# PART1.net
KiCad netlist of a schematic drawn in Altium Designer
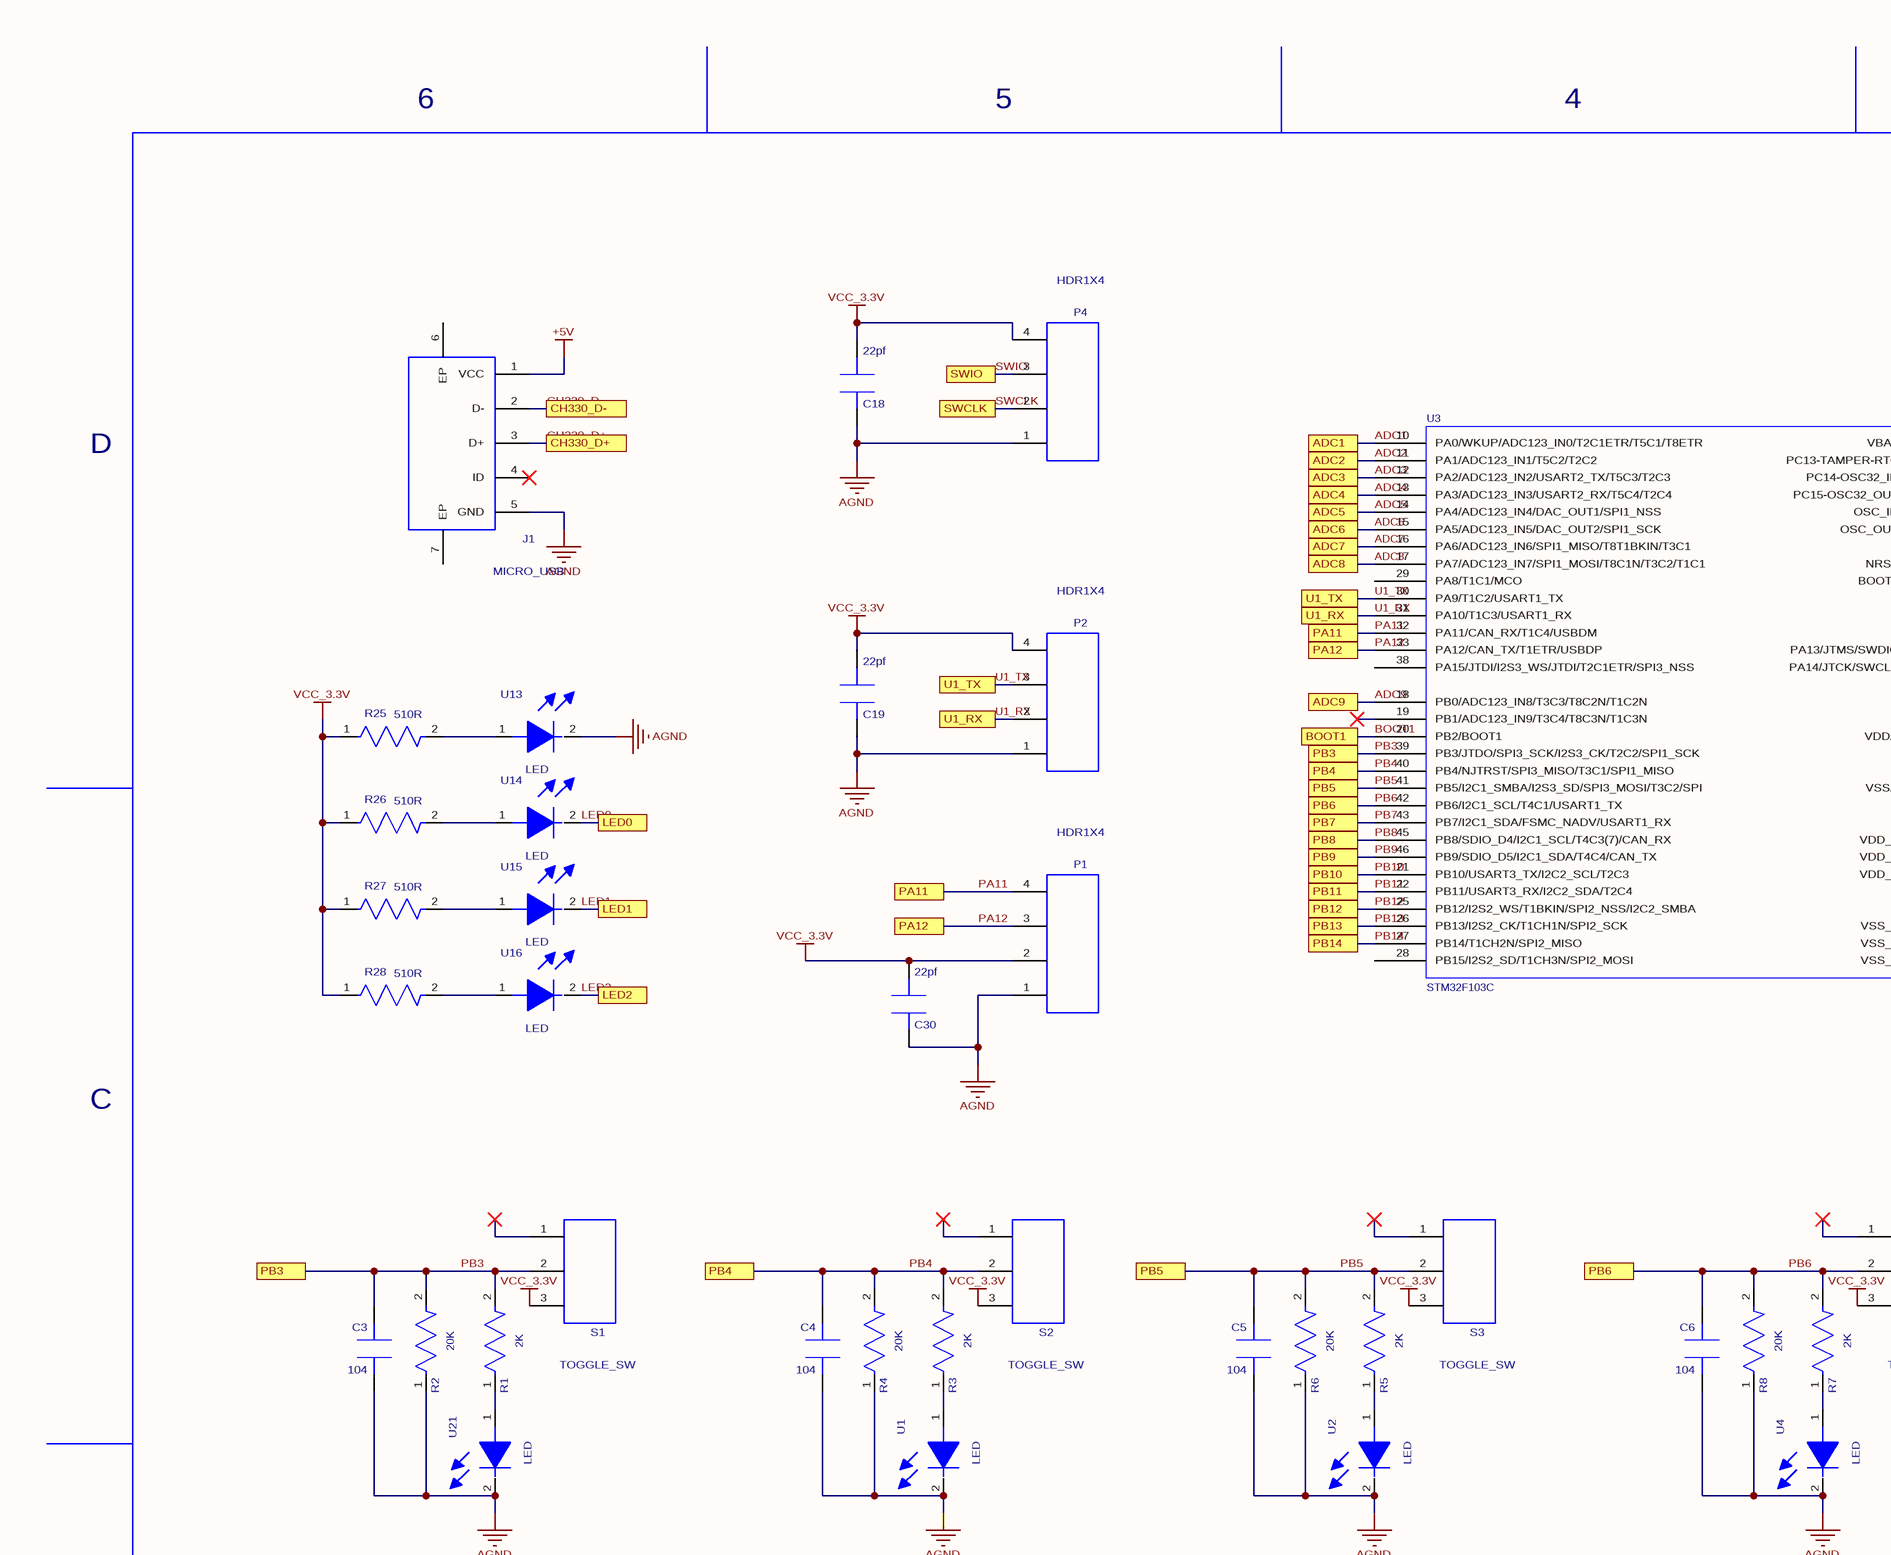
[diagram p0: PART1原.SchDoc, top left]
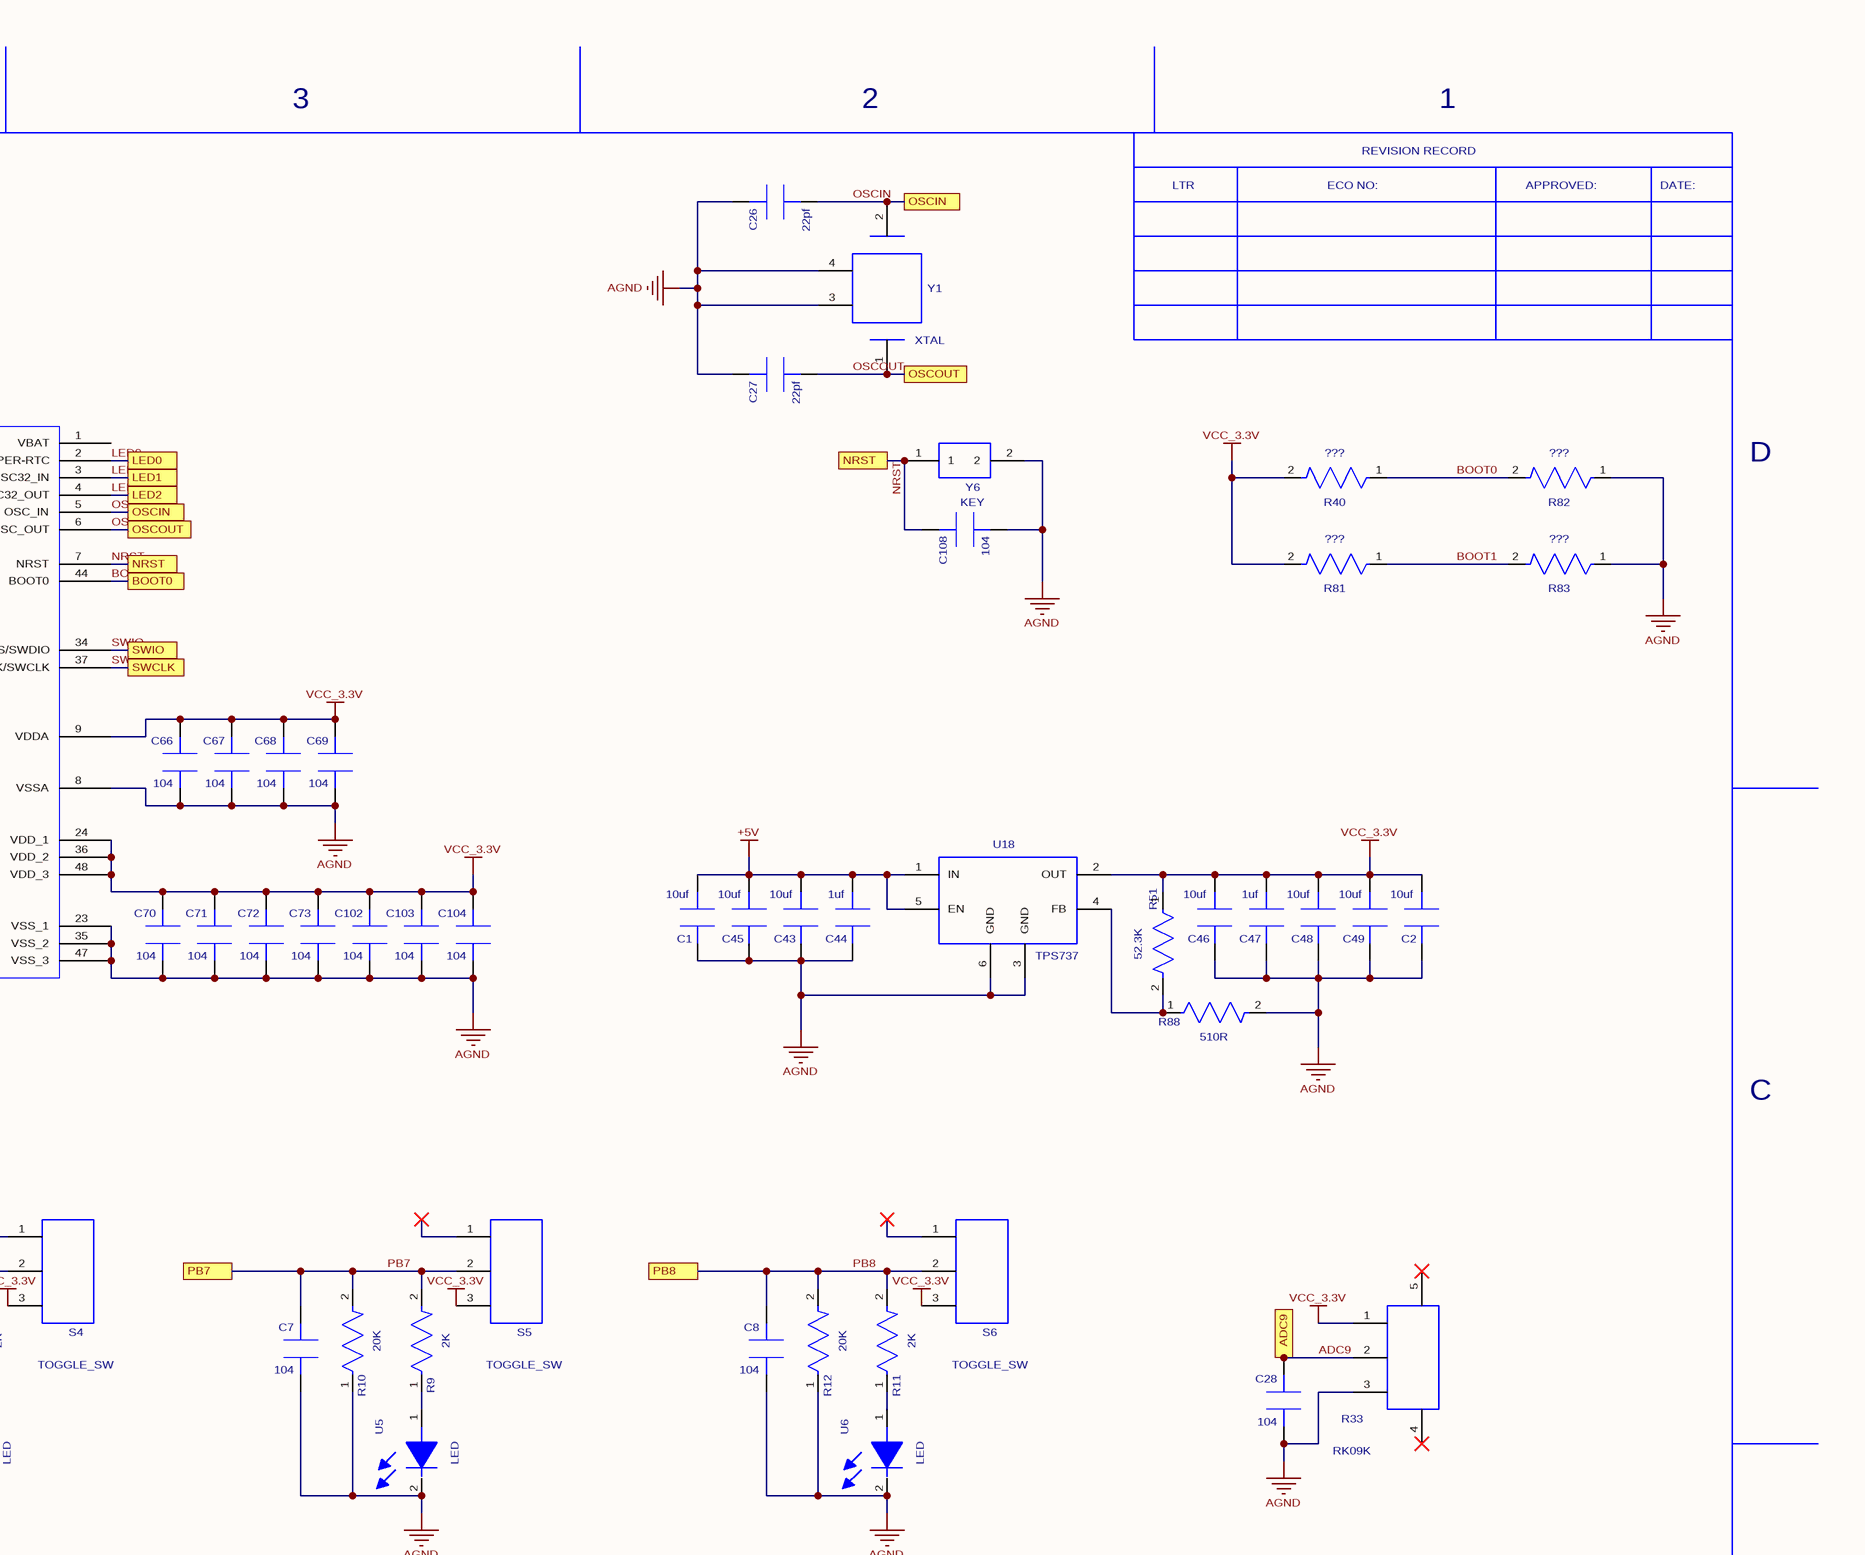
[diagram p1: PART1原.SchDoc, top right]
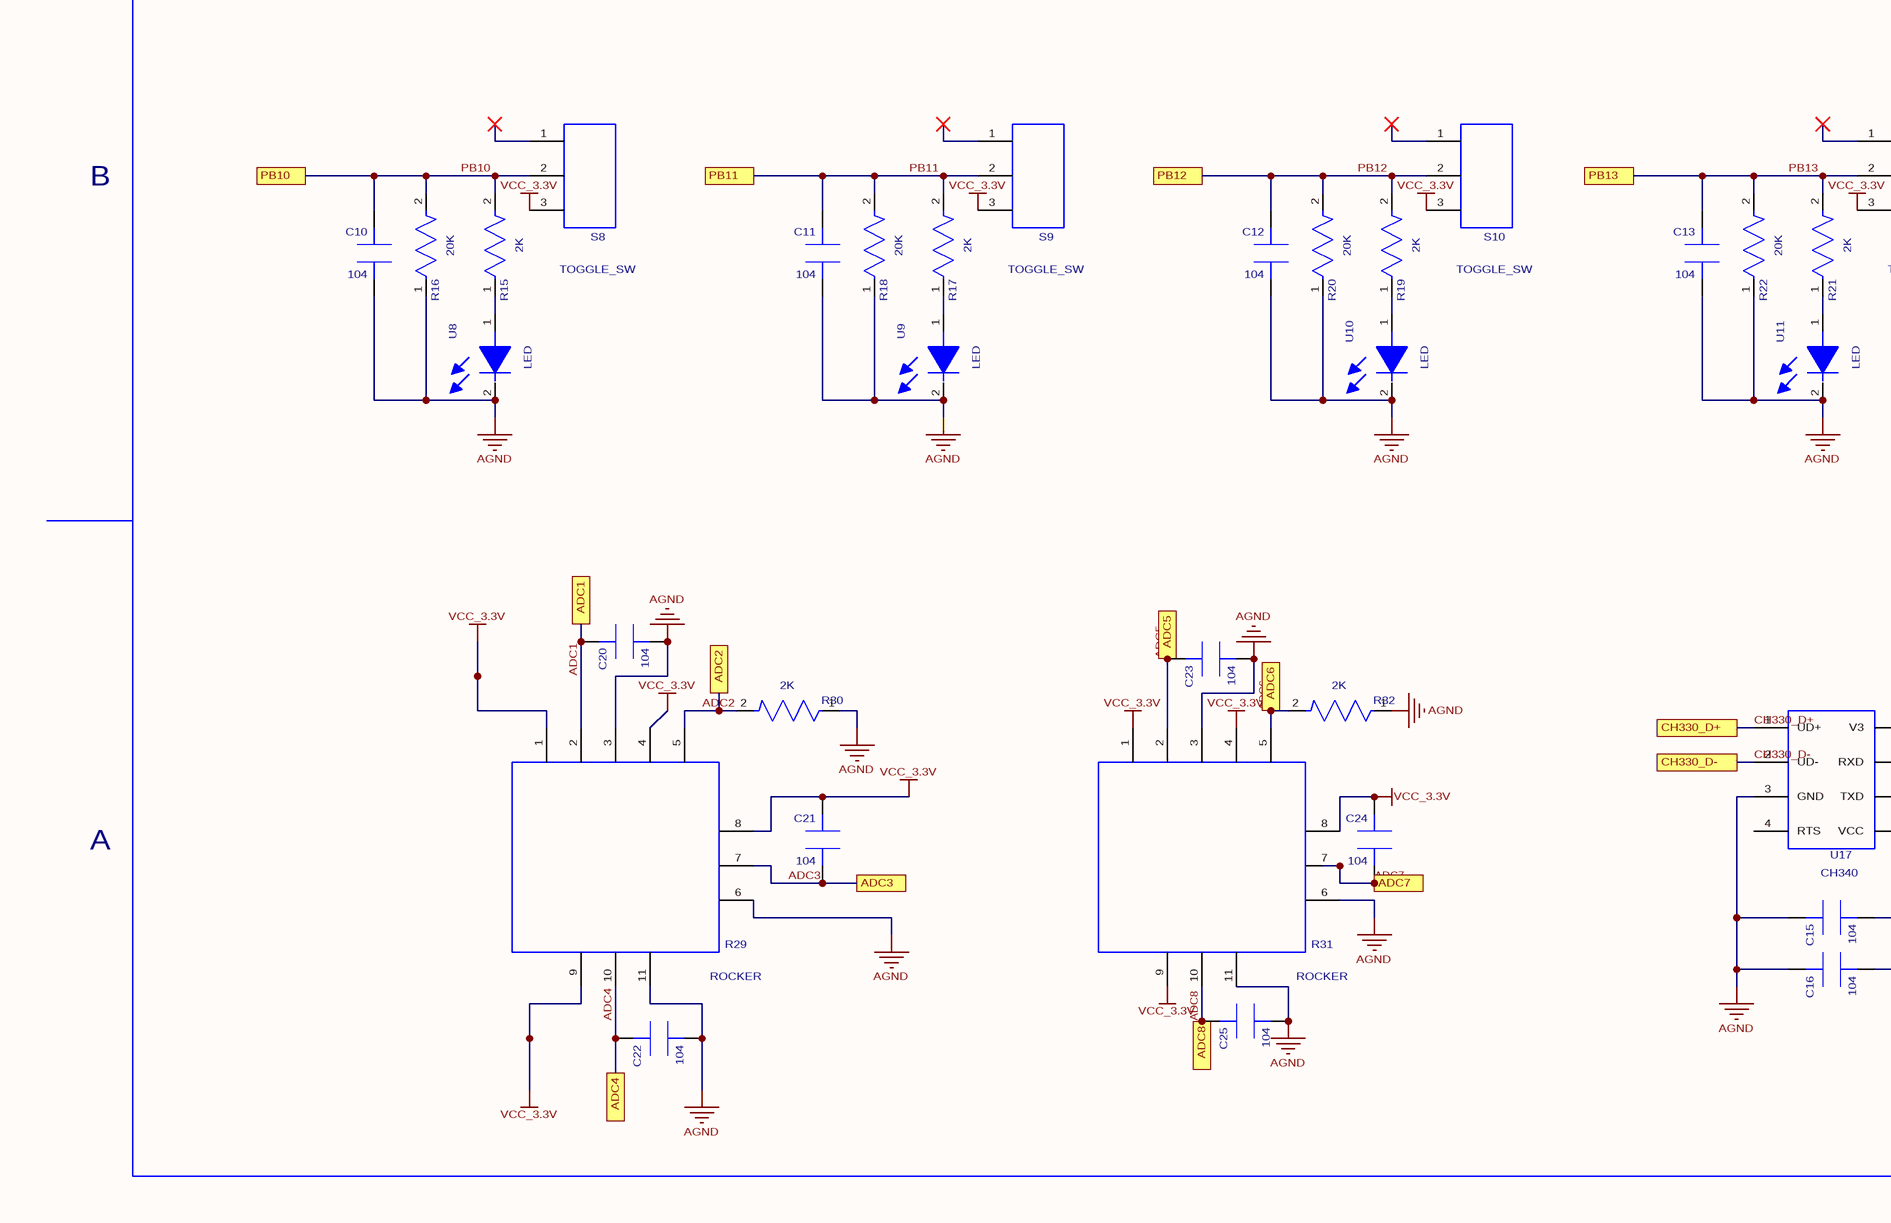
[diagram p2: PART1原.SchDoc, bottom left]
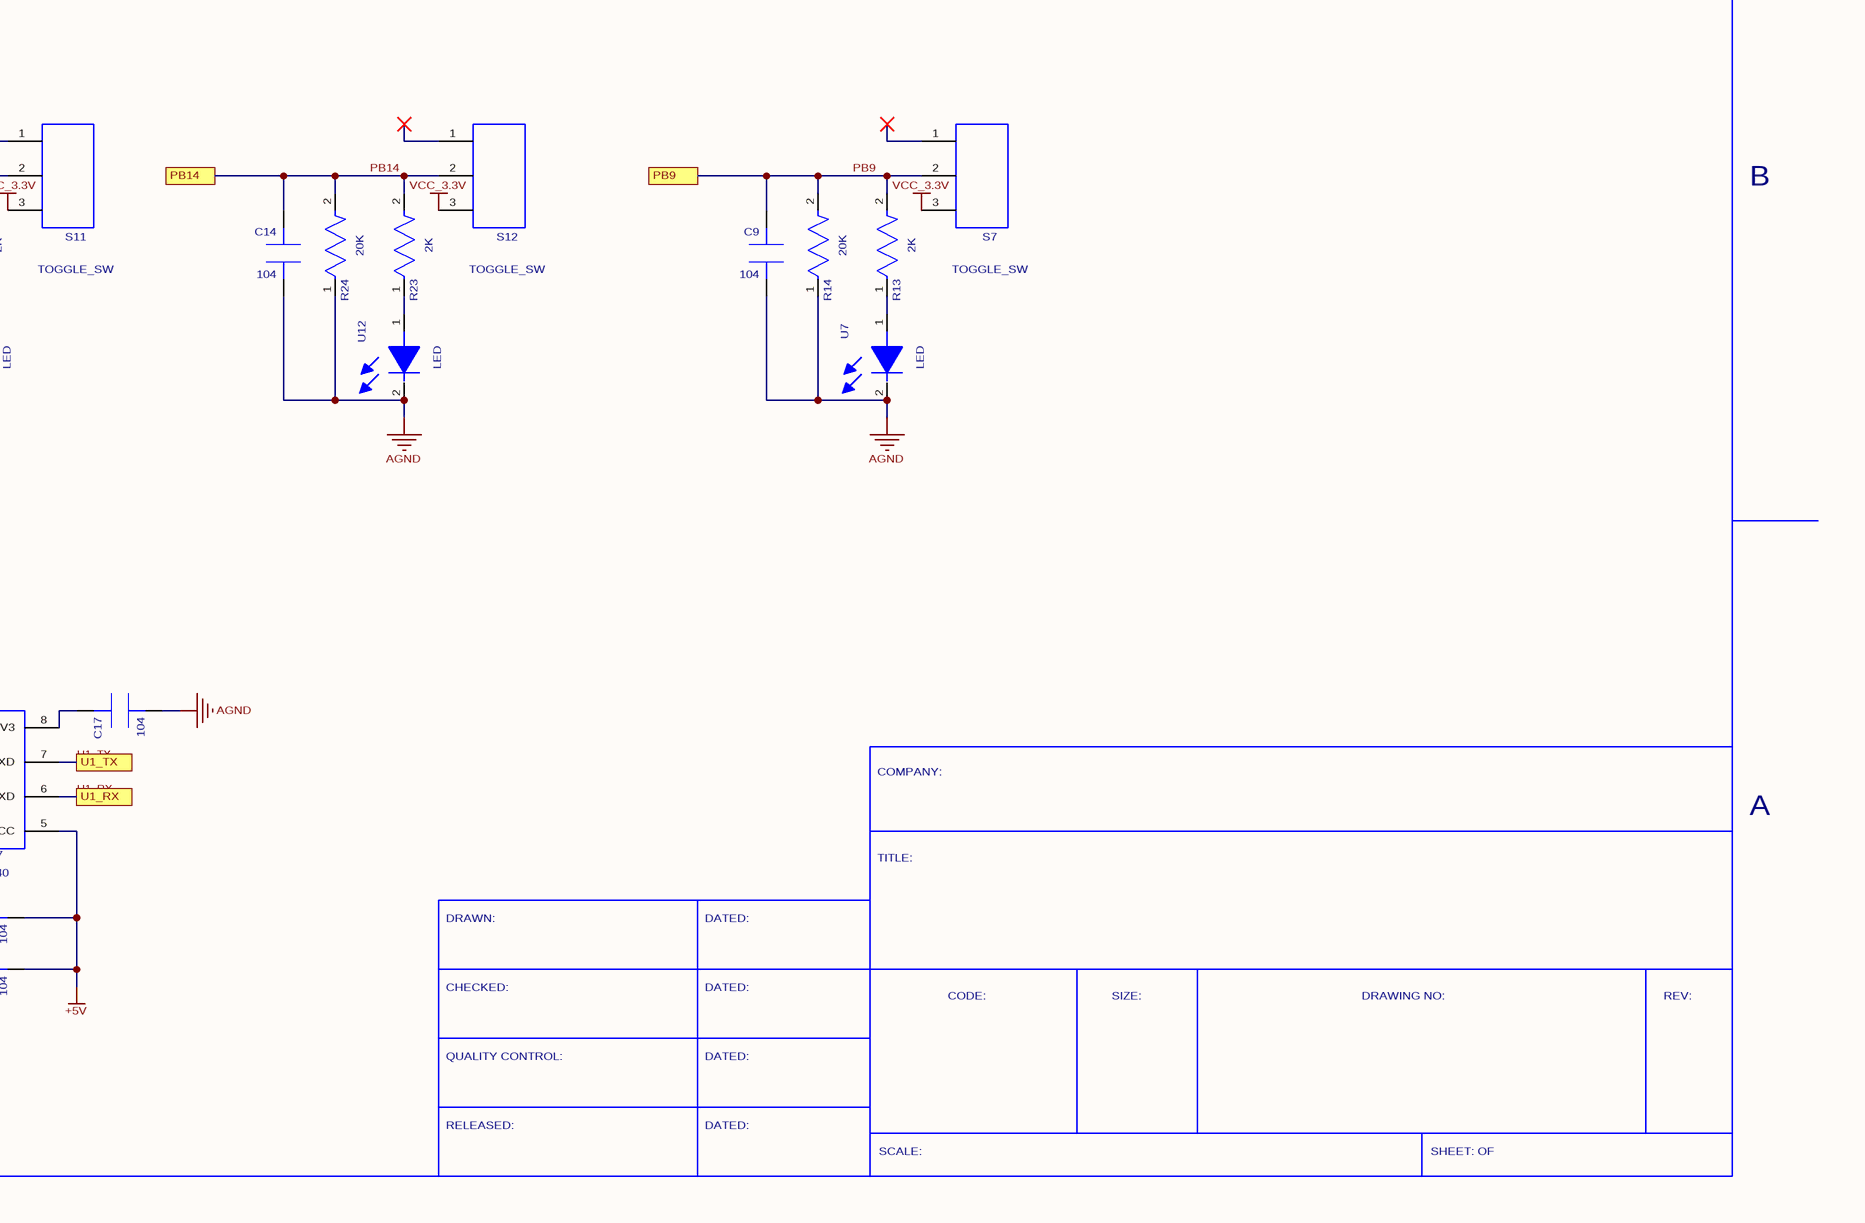
[diagram p3: PART1原.SchDoc, bottom right]

(export (version "E")
  (design (tool "Eeschema 10.0.6"))
  (components
    (comp (ref "C1")
      (value "10uf")
      (footprint "1206C")
      (description "RADIAL FILM CAPACITOR, MIL-SPEC SIZE CFR04R SIZE 'C'")
      (fields (field (name "TOLERANCE") "???") (field (name "PART NUMBER") "TBD"))
      (libsource (lib "*") (part "CAP-CFR04R-C"))
    )
    (comp (ref "C2")
      (value "10uf")
      (footprint "1206C")
      (description "RADIAL FILM CAPACITOR, MIL-SPEC SIZE CFR04R SIZE 'C'")
      (fields (field (name "TOLERANCE") "???") (field (name "PART NUMBER") "TBD"))
      (libsource (lib "*") (part "CAP-CFR04R-C"))
    )
    (comp (ref "C3")
      (value "104")
      (footprint "0603C")
      (description "RADIAL FILM CAPACITOR, MIL-SPEC SIZE CFR04R SIZE 'C'")
      (fields (field (name "TOLERANCE") "???") (field (name "PART NUMBER") "TBD"))
      (libsource (lib "*") (part "CAP-CFR04R-C"))
    )
    (comp (ref "C4")
      (value "104")
      (footprint "0603C")
      (description "RADIAL FILM CAPACITOR, MIL-SPEC SIZE CFR04R SIZE 'C'")
      (fields (field (name "TOLERANCE") "???") (field (name "PART NUMBER") "TBD"))
      (libsource (lib "*") (part "CAP-CFR04R-C"))
    )
    (comp (ref "C5")
      (value "104")
      (footprint "0603C")
      (description "RADIAL FILM CAPACITOR, MIL-SPEC SIZE CFR04R SIZE 'C'")
      (fields (field (name "TOLERANCE") "???") (field (name "PART NUMBER") "TBD"))
      (libsource (lib "*") (part "CAP-CFR04R-C"))
    )
    (comp (ref "C6")
      (value "104")
      (footprint "0603C")
      (description "RADIAL FILM CAPACITOR, MIL-SPEC SIZE CFR04R SIZE 'C'")
      (fields (field (name "TOLERANCE") "???") (field (name "PART NUMBER") "TBD"))
      (libsource (lib "*") (part "CAP-CFR04R-C"))
    )
    (comp (ref "C7")
      (value "104")
      (footprint "0603C")
      (description "RADIAL FILM CAPACITOR, MIL-SPEC SIZE CFR04R SIZE 'C'")
      (fields (field (name "TOLERANCE") "???") (field (name "PART NUMBER") "TBD"))
      (libsource (lib "*") (part "CAP-CFR04R-C"))
    )
    (comp (ref "C8")
      (value "104")
      (footprint "0603C")
      (description "RADIAL FILM CAPACITOR, MIL-SPEC SIZE CFR04R SIZE 'C'")
      (fields (field (name "TOLERANCE") "???") (field (name "PART NUMBER") "TBD"))
      (libsource (lib "*") (part "CAP-CFR04R-C"))
    )
    (comp (ref "C9")
      (value "104")
      (footprint "0603C")
      (description "RADIAL FILM CAPACITOR, MIL-SPEC SIZE CFR04R SIZE 'C'")
      (fields (field (name "TOLERANCE") "???") (field (name "PART NUMBER") "TBD"))
      (libsource (lib "*") (part "CAP-CFR04R-C"))
    )
    (comp (ref "C10")
      (value "104")
      (footprint "0603C")
      (description "RADIAL FILM CAPACITOR, MIL-SPEC SIZE CFR04R SIZE 'C'")
      (fields (field (name "TOLERANCE") "???") (field (name "PART NUMBER") "TBD"))
      (libsource (lib "*") (part "CAP-CFR04R-C"))
    )
    (comp (ref "C11")
      (value "104")
      (footprint "0603C")
      (description "RADIAL FILM CAPACITOR, MIL-SPEC SIZE CFR04R SIZE 'C'")
      (fields (field (name "TOLERANCE") "???") (field (name "PART NUMBER") "TBD"))
      (libsource (lib "*") (part "CAP-CFR04R-C"))
    )
    (comp (ref "C12")
      (value "104")
      (footprint "0603C")
      (description "RADIAL FILM CAPACITOR, MIL-SPEC SIZE CFR04R SIZE 'C'")
      (fields (field (name "TOLERANCE") "???") (field (name "PART NUMBER") "TBD"))
      (libsource (lib "*") (part "CAP-CFR04R-C"))
    )
    (comp (ref "C13")
      (value "104")
      (footprint "0603C")
      (description "RADIAL FILM CAPACITOR, MIL-SPEC SIZE CFR04R SIZE 'C'")
      (fields (field (name "TOLERANCE") "???") (field (name "PART NUMBER") "TBD"))
      (libsource (lib "*") (part "CAP-CFR04R-C"))
    )
    (comp (ref "C14")
      (value "104")
      (footprint "0603C")
      (description "RADIAL FILM CAPACITOR, MIL-SPEC SIZE CFR04R SIZE 'C'")
      (fields (field (name "TOLERANCE") "???") (field (name "PART NUMBER") "TBD"))
      (libsource (lib "*") (part "CAP-CFR04R-C"))
    )
    (comp (ref "C15")
      (value "104")
      (footprint "0603C")
      (description "RADIAL FILM CAPACITOR, MIL-SPEC SIZE CFR04R SIZE 'C'")
      (fields (field (name "TOLERANCE") "???") (field (name "PART NUMBER") "TBD"))
      (libsource (lib "*") (part "CAP-CFR04R-C"))
    )
    (comp (ref "C16")
      (value "104")
      (footprint "0805C")
      (description "RADIAL FILM CAPACITOR, MIL-SPEC SIZE CFR04R SIZE 'C'")
      (fields (field (name "TOLERANCE") "???") (field (name "PART NUMBER") "TBD"))
      (libsource (lib "*") (part "CAP-CFR04R-C"))
    )
    (comp (ref "C17")
      (value "104")
      (footprint "0603C")
      (description "RADIAL FILM CAPACITOR, MIL-SPEC SIZE CFR04R SIZE 'C'")
      (fields (field (name "TOLERANCE") "???") (field (name "PART NUMBER") "TBD"))
      (libsource (lib "*") (part "CAP-CFR04R-C"))
    )
    (comp (ref "C18")
      (value "22pf")
      (footprint "0603C")
      (description "RADIAL FILM CAPACITOR, MIL-SPEC SIZE CFR04R SIZE 'C'")
      (fields (field (name "TOLERANCE") "???") (field (name "PART NUMBER") "TBD"))
      (libsource (lib "*") (part "CAP-CFR04R-C"))
    )
    (comp (ref "C19")
      (value "22pf")
      (footprint "0603C")
      (description "RADIAL FILM CAPACITOR, MIL-SPEC SIZE CFR04R SIZE 'C'")
      (fields (field (name "TOLERANCE") "???") (field (name "PART NUMBER") "TBD"))
      (libsource (lib "*") (part "CAP-CFR04R-C"))
    )
    (comp (ref "C20")
      (value "104")
      (footprint "0805C")
      (description "RADIAL FILM CAPACITOR, MIL-SPEC SIZE CFR04R SIZE 'C'")
      (fields (field (name "TOLERANCE") "???") (field (name "PART NUMBER") "TBD"))
      (libsource (lib "*") (part "CAP-CFR04R-C"))
    )
    (comp (ref "C21")
      (value "104")
      (footprint "0805C")
      (description "RADIAL FILM CAPACITOR, MIL-SPEC SIZE CFR04R SIZE 'C'")
      (fields (field (name "TOLERANCE") "???") (field (name "PART NUMBER") "TBD"))
      (libsource (lib "*") (part "CAP-CFR04R-C"))
    )
    (comp (ref "C22")
      (value "104")
      (footprint "0805C")
      (description "RADIAL FILM CAPACITOR, MIL-SPEC SIZE CFR04R SIZE 'C'")
      (fields (field (name "TOLERANCE") "???") (field (name "PART NUMBER") "TBD"))
      (libsource (lib "*") (part "CAP-CFR04R-C"))
    )
    (comp (ref "C23")
      (value "104")
      (footprint "0805C")
      (description "RADIAL FILM CAPACITOR, MIL-SPEC SIZE CFR04R SIZE 'C'")
      (fields (field (name "TOLERANCE") "???") (field (name "PART NUMBER") "TBD"))
      (libsource (lib "*") (part "CAP-CFR04R-C"))
    )
    (comp (ref "C24")
      (value "104")
      (footprint "0805C")
      (description "RADIAL FILM CAPACITOR, MIL-SPEC SIZE CFR04R SIZE 'C'")
      (fields (field (name "TOLERANCE") "???") (field (name "PART NUMBER") "TBD"))
      (libsource (lib "*") (part "CAP-CFR04R-C"))
    )
    (comp (ref "C25")
      (value "104")
      (footprint "0805C")
      (description "RADIAL FILM CAPACITOR, MIL-SPEC SIZE CFR04R SIZE 'C'")
      (fields (field (name "TOLERANCE") "???") (field (name "PART NUMBER") "TBD"))
      (libsource (lib "*") (part "CAP-CFR04R-C"))
    )
    (comp (ref "C26")
      (value "22pf")
      (footprint "0603C")
      (description "RADIAL FILM CAPACITOR, MIL-SPEC SIZE CFR04R SIZE 'C'")
      (fields (field (name "TOLERANCE") "???") (field (name "PART NUMBER") "TBD"))
      (libsource (lib "*") (part "CAP-CFR04R-C"))
    )
    (comp (ref "C27")
      (value "22pf")
      (footprint "0603C")
      (description "RADIAL FILM CAPACITOR, MIL-SPEC SIZE CFR04R SIZE 'C'")
      (fields (field (name "TOLERANCE") "???") (field (name "PART NUMBER") "TBD"))
      (libsource (lib "*") (part "CAP-CFR04R-C"))
    )
    (comp (ref "C28")
      (value "104")
      (footprint "0603C")
      (description "RADIAL FILM CAPACITOR, MIL-SPEC SIZE CFR04R SIZE 'C'")
      (fields (field (name "TOLERANCE") "???") (field (name "PART NUMBER") "TBD"))
      (libsource (lib "*") (part "CAP-CFR04R-C"))
    )
    (comp (ref "C30")
      (value "22pf")
      (footprint "0603C")
      (description "RADIAL FILM CAPACITOR, MIL-SPEC SIZE CFR04R SIZE 'C'")
      (fields (field (name "TOLERANCE") "???") (field (name "PART NUMBER") "TBD"))
      (libsource (lib "*") (part "CAP-CFR04R-C"))
    )
    (comp (ref "C43")
      (value "10uf")
      (footprint "1206C")
      (description "RADIAL FILM CAPACITOR, MIL-SPEC SIZE CFR04R SIZE 'C'")
      (fields (field (name "TOLERANCE") "???") (field (name "PART NUMBER") "TBD"))
      (libsource (lib "*") (part "CAP-CFR04R-C"))
    )
    (comp (ref "C44")
      (value "1uf")
      (footprint "0805C")
      (description "RADIAL FILM CAPACITOR, MIL-SPEC SIZE CFR04R SIZE 'C'")
      (fields (field (name "TOLERANCE") "???") (field (name "PART NUMBER") "TBD"))
      (libsource (lib "*") (part "CAP-CFR04R-C"))
    )
    (comp (ref "C45")
      (value "10uf")
      (footprint "1206C")
      (description "RADIAL FILM CAPACITOR, MIL-SPEC SIZE CFR04R SIZE 'C'")
      (fields (field (name "TOLERANCE") "???") (field (name "PART NUMBER") "TBD"))
      (libsource (lib "*") (part "CAP-CFR04R-C"))
    )
    (comp (ref "C46")
      (value "10uf")
      (footprint "1206C")
      (description "RADIAL FILM CAPACITOR, MIL-SPEC SIZE CFR04R SIZE 'C'")
      (fields (field (name "TOLERANCE") "???") (field (name "PART NUMBER") "TBD"))
      (libsource (lib "*") (part "CAP-CFR04R-C"))
    )
    (comp (ref "C47")
      (value "1uf")
      (footprint "0805C")
      (description "RADIAL FILM CAPACITOR, MIL-SPEC SIZE CFR04R SIZE 'C'")
      (fields (field (name "TOLERANCE") "???") (field (name "PART NUMBER") "TBD"))
      (libsource (lib "*") (part "CAP-CFR04R-C"))
    )
    (comp (ref "C48")
      (value "10uf")
      (footprint "1206C")
      (description "RADIAL FILM CAPACITOR, MIL-SPEC SIZE CFR04R SIZE 'C'")
      (fields (field (name "TOLERANCE") "???") (field (name "PART NUMBER") "TBD"))
      (libsource (lib "*") (part "CAP-CFR04R-C"))
    )
    (comp (ref "C49")
      (value "10uf")
      (footprint "1206C")
      (description "RADIAL FILM CAPACITOR, MIL-SPEC SIZE CFR04R SIZE 'C'")
      (fields (field (name "TOLERANCE") "???") (field (name "PART NUMBER") "TBD"))
      (libsource (lib "*") (part "CAP-CFR04R-C"))
    )
    (comp (ref "C66")
      (value "104")
      (footprint "0805C")
      (description "RADIAL FILM CAPACITOR, MIL-SPEC SIZE CFR04R SIZE 'C'")
      (fields (field (name "TOLERANCE") "???") (field (name "PART NUMBER") "TBD"))
      (libsource (lib "*") (part "CAP-CFR04R-C"))
    )
    (comp (ref "C67")
      (value "104")
      (footprint "0805C")
      (description "RADIAL FILM CAPACITOR, MIL-SPEC SIZE CFR04R SIZE 'C'")
      (fields (field (name "TOLERANCE") "???") (field (name "PART NUMBER") "TBD"))
      (libsource (lib "*") (part "CAP-CFR04R-C"))
    )
    (comp (ref "C68")
      (value "104")
      (footprint "0805C")
      (description "RADIAL FILM CAPACITOR, MIL-SPEC SIZE CFR04R SIZE 'C'")
      (fields (field (name "TOLERANCE") "???") (field (name "PART NUMBER") "TBD"))
      (libsource (lib "*") (part "CAP-CFR04R-C"))
    )
    (comp (ref "C69")
      (value "104")
      (footprint "0805C")
      (description "RADIAL FILM CAPACITOR, MIL-SPEC SIZE CFR04R SIZE 'C'")
      (fields (field (name "TOLERANCE") "???") (field (name "PART NUMBER") "TBD"))
      (libsource (lib "*") (part "CAP-CFR04R-C"))
    )
    (comp (ref "C70")
      (value "104")
      (footprint "0805C")
      (description "RADIAL FILM CAPACITOR, MIL-SPEC SIZE CFR04R SIZE 'C'")
      (fields (field (name "TOLERANCE") "???") (field (name "PART NUMBER") "TBD"))
      (libsource (lib "*") (part "CAP-CFR04R-C"))
    )
    (comp (ref "C71")
      (value "104")
      (footprint "0805C")
      (description "RADIAL FILM CAPACITOR, MIL-SPEC SIZE CFR04R SIZE 'C'")
      (fields (field (name "TOLERANCE") "???") (field (name "PART NUMBER") "TBD"))
      (libsource (lib "*") (part "CAP-CFR04R-C"))
    )
    (comp (ref "C72")
      (value "104")
      (footprint "0805C")
      (description "RADIAL FILM CAPACITOR, MIL-SPEC SIZE CFR04R SIZE 'C'")
      (fields (field (name "TOLERANCE") "???") (field (name "PART NUMBER") "TBD"))
      (libsource (lib "*") (part "CAP-CFR04R-C"))
    )
    (comp (ref "C73")
      (value "104")
      (footprint "0805C")
      (description "RADIAL FILM CAPACITOR, MIL-SPEC SIZE CFR04R SIZE 'C'")
      (fields (field (name "TOLERANCE") "???") (field (name "PART NUMBER") "TBD"))
      (libsource (lib "*") (part "CAP-CFR04R-C"))
    )
    (comp (ref "C102")
      (value "104")
      (footprint "0805C")
      (description "RADIAL FILM CAPACITOR, MIL-SPEC SIZE CFR04R SIZE 'C'")
      (fields (field (name "TOLERANCE") "???") (field (name "PART NUMBER") "TBD"))
      (libsource (lib "*") (part "CAP-CFR04R-C"))
    )
    (comp (ref "C103")
      (value "104")
      (footprint "0805C")
      (description "RADIAL FILM CAPACITOR, MIL-SPEC SIZE CFR04R SIZE 'C'")
      (fields (field (name "TOLERANCE") "???") (field (name "PART NUMBER") "TBD"))
      (libsource (lib "*") (part "CAP-CFR04R-C"))
    )
    (comp (ref "C104")
      (value "104")
      (footprint "0805C")
      (description "RADIAL FILM CAPACITOR, MIL-SPEC SIZE CFR04R SIZE 'C'")
      (fields (field (name "TOLERANCE") "???") (field (name "PART NUMBER") "TBD"))
      (libsource (lib "*") (part "CAP-CFR04R-C"))
    )
    (comp (ref "C108")
      (value "104")
      (footprint "0805C")
      (description "RADIAL FILM CAPACITOR, MIL-SPEC SIZE CFR04R SIZE 'C'")
      (fields (field (name "TOLERANCE") "???") (field (name "PART NUMBER") "TBD"))
      (libsource (lib "*") (part "CAP-CFR04R-C"))
    )
    (comp (ref "J1") (value "MICRO_USB") (footprint "MICRO_USB") (libsource (lib "*") (part "MICRO_USB")))
    (comp (ref "P1") (value "HDR1X4") (footprint "HDR1X4(2)") (libsource (lib "*") (part "HDR1X4")))
    (comp (ref "P2") (value "HDR1X4") (footprint "HDR1X4(2)") (libsource (lib "*") (part "HDR1X4")))
    (comp (ref "P4") (value "HDR1X4") (footprint "HDR1X4(2)") (libsource (lib "*") (part "HDR1X4")))
    (comp (ref "R1")
      (value "2K")
      (footprint "0603R")
      (description "WIRE WOUND RESISTOR 3.4 X 7.05 MM")
      (fields (field (name "Comment") "RES-WR1"))
      (libsource (lib "*") (part "RES-WR1"))
    )
    (comp (ref "R2")
      (value "20K")
      (footprint "0603R")
      (description "WIRE WOUND RESISTOR 3.4 X 7.05 MM")
      (fields (field (name "Comment") "RES-WR1"))
      (libsource (lib "*") (part "RES-WR1"))
    )
    (comp (ref "R3")
      (value "2K")
      (footprint "0603R")
      (description "WIRE WOUND RESISTOR 3.4 X 7.05 MM")
      (fields (field (name "Comment") "RES-WR1"))
      (libsource (lib "*") (part "RES-WR1"))
    )
    (comp (ref "R4")
      (value "20K")
      (footprint "0603R")
      (description "WIRE WOUND RESISTOR 3.4 X 7.05 MM")
      (fields (field (name "Comment") "RES-WR1"))
      (libsource (lib "*") (part "RES-WR1"))
    )
    (comp (ref "R5")
      (value "2K")
      (footprint "0603R")
      (description "WIRE WOUND RESISTOR 3.4 X 7.05 MM")
      (fields (field (name "Comment") "RES-WR1"))
      (libsource (lib "*") (part "RES-WR1"))
    )
    (comp (ref "R6")
      (value "20K")
      (footprint "0603R")
      (description "WIRE WOUND RESISTOR 3.4 X 7.05 MM")
      (fields (field (name "Comment") "RES-WR1"))
      (libsource (lib "*") (part "RES-WR1"))
    )
    (comp (ref "R7")
      (value "2K")
      (footprint "0603R")
      (description "WIRE WOUND RESISTOR 3.4 X 7.05 MM")
      (fields (field (name "Comment") "RES-WR1"))
      (libsource (lib "*") (part "RES-WR1"))
    )
    (comp (ref "R8")
      (value "20K")
      (footprint "0603R")
      (description "WIRE WOUND RESISTOR 3.4 X 7.05 MM")
      (fields (field (name "Comment") "RES-WR1"))
      (libsource (lib "*") (part "RES-WR1"))
    )
    (comp (ref "R9")
      (value "2K")
      (footprint "0603R")
      (description "WIRE WOUND RESISTOR 3.4 X 7.05 MM")
      (fields (field (name "Comment") "RES-WR1"))
      (libsource (lib "*") (part "RES-WR1"))
    )
    (comp (ref "R10")
      (value "20K")
      (footprint "0603R")
      (description "WIRE WOUND RESISTOR 3.4 X 7.05 MM")
      (fields (field (name "Comment") "RES-WR1"))
      (libsource (lib "*") (part "RES-WR1"))
    )
    (comp (ref "R11")
      (value "2K")
      (footprint "0603R")
      (description "WIRE WOUND RESISTOR 3.4 X 7.05 MM")
      (fields (field (name "Comment") "RES-WR1"))
      (libsource (lib "*") (part "RES-WR1"))
    )
    (comp (ref "R12")
      (value "20K")
      (footprint "0603R")
      (description "WIRE WOUND RESISTOR 3.4 X 7.05 MM")
      (fields (field (name "Comment") "RES-WR1"))
      (libsource (lib "*") (part "RES-WR1"))
    )
    (comp (ref "R13")
      (value "2K")
      (footprint "0603R")
      (description "WIRE WOUND RESISTOR 3.4 X 7.05 MM")
      (fields (field (name "Comment") "RES-WR1"))
      (libsource (lib "*") (part "RES-WR1"))
    )
    (comp (ref "R14")
      (value "20K")
      (footprint "0603R")
      (description "WIRE WOUND RESISTOR 3.4 X 7.05 MM")
      (fields (field (name "Comment") "RES-WR1"))
      (libsource (lib "*") (part "RES-WR1"))
    )
    (comp (ref "R15")
      (value "2K")
      (footprint "0603R")
      (description "WIRE WOUND RESISTOR 3.4 X 7.05 MM")
      (fields (field (name "Comment") "RES-WR1"))
      (libsource (lib "*") (part "RES-WR1"))
    )
    (comp (ref "R16")
      (value "20K")
      (footprint "0603R")
      (description "WIRE WOUND RESISTOR 3.4 X 7.05 MM")
      (fields (field (name "Comment") "RES-WR1"))
      (libsource (lib "*") (part "RES-WR1"))
    )
    (comp (ref "R17")
      (value "2K")
      (footprint "0603R")
      (description "WIRE WOUND RESISTOR 3.4 X 7.05 MM")
      (fields (field (name "Comment") "RES-WR1"))
      (libsource (lib "*") (part "RES-WR1"))
    )
    (comp (ref "R18")
      (value "20K")
      (footprint "0603R")
      (description "WIRE WOUND RESISTOR 3.4 X 7.05 MM")
      (fields (field (name "Comment") "RES-WR1"))
      (libsource (lib "*") (part "RES-WR1"))
    )
    (comp (ref "R19")
      (value "2K")
      (footprint "0603R")
      (description "WIRE WOUND RESISTOR 3.4 X 7.05 MM")
      (fields (field (name "Comment") "RES-WR1"))
      (libsource (lib "*") (part "RES-WR1"))
    )
    (comp (ref "R20")
      (value "20K")
      (footprint "0603R")
      (description "WIRE WOUND RESISTOR 3.4 X 7.05 MM")
      (fields (field (name "Comment") "RES-WR1"))
      (libsource (lib "*") (part "RES-WR1"))
    )
    (comp (ref "R21")
      (value "2K")
      (footprint "0603R")
      (description "WIRE WOUND RESISTOR 3.4 X 7.05 MM")
      (fields (field (name "Comment") "RES-WR1"))
      (libsource (lib "*") (part "RES-WR1"))
    )
    (comp (ref "R22")
      (value "20K")
      (footprint "0603R")
      (description "WIRE WOUND RESISTOR 3.4 X 7.05 MM")
      (fields (field (name "Comment") "RES-WR1"))
      (libsource (lib "*") (part "RES-WR1"))
    )
    (comp (ref "R23")
      (value "2K")
      (footprint "0603R")
      (description "WIRE WOUND RESISTOR 3.4 X 7.05 MM")
      (fields (field (name "Comment") "RES-WR1"))
      (libsource (lib "*") (part "RES-WR1"))
    )
    (comp (ref "R24")
      (value "20K")
      (footprint "0603R")
      (description "WIRE WOUND RESISTOR 3.4 X 7.05 MM")
      (fields (field (name "Comment") "RES-WR1"))
      (libsource (lib "*") (part "RES-WR1"))
    )
    (comp (ref "R25")
      (value "510R")
      (footprint "0603R")
      (description "WIRE WOUND RESISTOR 3.4 X 7.05 MM")
      (fields (field (name "Comment") "RES-WR1"))
      (libsource (lib "*") (part "RES-WR1"))
    )
    (comp (ref "R26")
      (value "510R")
      (footprint "0603R")
      (description "WIRE WOUND RESISTOR 3.4 X 7.05 MM")
      (fields (field (name "Comment") "RES-WR1"))
      (libsource (lib "*") (part "RES-WR1"))
    )
    (comp (ref "R27")
      (value "510R")
      (footprint "0603R")
      (description "WIRE WOUND RESISTOR 3.4 X 7.05 MM")
      (fields (field (name "Comment") "RES-WR1"))
      (libsource (lib "*") (part "RES-WR1"))
    )
    (comp (ref "R28")
      (value "510R")
      (footprint "0603R")
      (description "WIRE WOUND RESISTOR 3.4 X 7.05 MM")
      (fields (field (name "Comment") "RES-WR1"))
      (libsource (lib "*") (part "RES-WR1"))
    )
    (comp (ref "R29") (value "ROCKER") (footprint "ROCKER") (libsource (lib "*") (part "ROCKER")))
    (comp (ref "R30")
      (value "2K")
      (footprint "0603R")
      (description "WIRE WOUND RESISTOR 3.4 X 7.05 MM")
      (fields (field (name "Comment") "RES-WR1"))
      (libsource (lib "*") (part "RES-WR1"))
    )
    (comp (ref "R31") (value "ROCKER") (footprint "ROCKER") (libsource (lib "*") (part "ROCKER")))
    (comp (ref "R32")
      (value "2K")
      (footprint "0603R")
      (description "WIRE WOUND RESISTOR 3.4 X 7.05 MM")
      (fields (field (name "Comment") "RES-WR1"))
      (libsource (lib "*") (part "RES-WR1"))
    )
    (comp (ref "R33") (value "RK09K") (footprint "RK09K_RES") (libsource (lib "*") (part "RK09K")))
    (comp (ref "R40")
      (value "???")
      (footprint "0603R")
      (description "WIRE WOUND RESISTOR 3.4 X 7.05 MM")
      (fields (field (name "Comment") "RES-WR1"))
      (libsource (lib "*") (part "RES-WR1"))
    )
    (comp (ref "R51")
      (value "52.3K")
      (footprint "0603R")
      (description "WIRE WOUND RESISTOR 3.4 X 7.05 MM")
      (fields (field (name "Comment") "RES-WR1"))
      (libsource (lib "*") (part "RES-WR1"))
    )
    (comp (ref "R81")
      (value "???")
      (footprint "0603R")
      (description "WIRE WOUND RESISTOR 3.4 X 7.05 MM")
      (fields (field (name "Comment") "RES-WR1"))
      (libsource (lib "*") (part "RES-WR1"))
    )
    (comp (ref "R82")
      (value "???")
      (footprint "0603R")
      (description "WIRE WOUND RESISTOR 3.4 X 7.05 MM")
      (fields (field (name "Comment") "RES-WR1"))
      (libsource (lib "*") (part "RES-WR1"))
    )
    (comp (ref "R83")
      (value "???")
      (footprint "0603R")
      (description "WIRE WOUND RESISTOR 3.4 X 7.05 MM")
      (fields (field (name "Comment") "RES-WR1"))
      (libsource (lib "*") (part "RES-WR1"))
    )
    (comp (ref "R88")
      (value "510R")
      (footprint "0603R")
      (description "WIRE WOUND RESISTOR 3.4 X 7.05 MM")
      (fields (field (name "Comment") "RES-WR1"))
      (libsource (lib "*") (part "RES-WR1"))
    )
    (comp (ref "S1") (value "TOGGLE_SW") (footprint "TOGGLE_SWITCH") (libsource (lib "*") (part "TOGGLE_SW")))
    (comp (ref "S2") (value "TOGGLE_SW") (footprint "TOGGLE_SWITCH") (libsource (lib "*") (part "TOGGLE_SW")))
    (comp (ref "S3") (value "TOGGLE_SW") (footprint "TOGGLE_SWITCH") (libsource (lib "*") (part "TOGGLE_SW")))
    (comp (ref "S4") (value "TOGGLE_SW") (footprint "TOGGLE_SWITCH") (libsource (lib "*") (part "TOGGLE_SW")))
    (comp (ref "S5") (value "TOGGLE_SW") (footprint "TOGGLE_SWITCH") (libsource (lib "*") (part "TOGGLE_SW")))
    (comp (ref "S6") (value "TOGGLE_SW") (footprint "TOGGLE_SWITCH") (libsource (lib "*") (part "TOGGLE_SW")))
    (comp (ref "S7") (value "TOGGLE_SW") (footprint "TOGGLE_SWITCH") (libsource (lib "*") (part "TOGGLE_SW")))
    (comp (ref "S8") (value "TOGGLE_SW") (footprint "TOGGLE_SWITCH") (libsource (lib "*") (part "TOGGLE_SW")))
    (comp (ref "S9") (value "TOGGLE_SW") (footprint "TOGGLE_SWITCH") (libsource (lib "*") (part "TOGGLE_SW")))
    (comp (ref "S10")
      (value "TOGGLE_SW")
      (footprint "TOGGLE_SWITCH")
      (libsource (lib "*") (part "TOGGLE_SW"))
    )
    (comp (ref "S11")
      (value "TOGGLE_SW")
      (footprint "TOGGLE_SWITCH")
      (libsource (lib "*") (part "TOGGLE_SW"))
    )
    (comp (ref "S12")
      (value "TOGGLE_SW")
      (footprint "TOGGLE_SWITCH")
      (libsource (lib "*") (part "TOGGLE_SW"))
    )
    (comp (ref "U1")
      (value "DS0")
      (footprint "0805D")
      (fields (field (name "COMMENT_1") "LED"))
      (libsource (lib "*") (part "LED"))
    )
    (comp (ref "U2")
      (value "DS0")
      (footprint "0805D")
      (fields (field (name "COMMENT_1") "LED"))
      (libsource (lib "*") (part "LED"))
    )
    (comp (ref "U3")
      (value "STM32F103C")
      (footprint "LQFP-48_M")
      (description "STM32单片机48引脚")
      (libsource (lib "*") (part "STM32F103C"))
    )
    (comp (ref "U4")
      (value "DS0")
      (footprint "0805D")
      (fields (field (name "COMMENT_1") "LED"))
      (libsource (lib "*") (part "LED"))
    )
    (comp (ref "U5")
      (value "DS0")
      (footprint "0805D")
      (fields (field (name "COMMENT_1") "LED"))
      (libsource (lib "*") (part "LED"))
    )
    (comp (ref "U6")
      (value "DS0")
      (footprint "0805D")
      (fields (field (name "COMMENT_1") "LED"))
      (libsource (lib "*") (part "LED"))
    )
    (comp (ref "U7")
      (value "DS0")
      (footprint "0805D")
      (fields (field (name "COMMENT_1") "LED"))
      (libsource (lib "*") (part "LED"))
    )
    (comp (ref "U8")
      (value "DS0")
      (footprint "0805D")
      (fields (field (name "COMMENT_1") "LED"))
      (libsource (lib "*") (part "LED"))
    )
    (comp (ref "U9")
      (value "DS0")
      (footprint "0805D")
      (fields (field (name "COMMENT_1") "LED"))
      (libsource (lib "*") (part "LED"))
    )
    (comp (ref "U10")
      (value "DS0")
      (footprint "0805D")
      (fields (field (name "COMMENT_1") "LED"))
      (libsource (lib "*") (part "LED"))
    )
    (comp (ref "U11")
      (value "DS0")
      (footprint "0805D")
      (fields (field (name "COMMENT_1") "LED"))
      (libsource (lib "*") (part "LED"))
    )
    (comp (ref "U12")
      (value "DS0")
      (footprint "0805D")
      (fields (field (name "COMMENT_1") "LED"))
      (libsource (lib "*") (part "LED"))
    )
    (comp (ref "U13")
      (value "DS0")
      (footprint "0805D")
      (fields (field (name "COMMENT_1") "LED"))
      (libsource (lib "*") (part "LED"))
    )
    (comp (ref "U14")
      (value "DS0")
      (footprint "0805D")
      (fields (field (name "COMMENT_1") "LED"))
      (libsource (lib "*") (part "LED"))
    )
    (comp (ref "U15")
      (value "DS0")
      (footprint "0805D")
      (fields (field (name "COMMENT_1") "LED"))
      (libsource (lib "*") (part "LED"))
    )
    (comp (ref "U16")
      (value "DS0")
      (footprint "0805D")
      (fields (field (name "COMMENT_1") "LED"))
      (libsource (lib "*") (part "LED"))
    )
    (comp (ref "U17") (value "CH340") (footprint "SOP_8") (libsource (lib "*") (part "CH330")))
    (comp (ref "U18")
      (value "TPS737")
      (footprint "SOT-223-6_L6.5-W3.5-P1.27-BL")
      (libsource (lib "*") (part "TPS737"))
    )
    (comp (ref "U21")
      (value "DS0")
      (footprint "0805D")
      (fields (field (name "COMMENT_1") "LED"))
      (libsource (lib "*") (part "LED"))
    )
    (comp (ref "Y1") (value "XTAL") (footprint "XTAL3") (libsource (lib "PCB_Project1") (part "XTAL")))
    (comp (ref "Y6") (value "KEY") (footprint "KEY_3_6_2.5") (libsource (lib "*") (part "KEY")))
  )
  (nets
    (net (code "1") (name "+5V") (class "Default")
      (node (ref "C1") (pin "2") (pinfunction "2_2") (pintype "passive"))
      (node (ref "C15") (pin "2") (pinfunction "2_2") (pintype "passive"))
      (node (ref "C16") (pin "2") (pinfunction "2_2") (pintype "passive"))
      (node (ref "C43") (pin "2") (pinfunction "2_2") (pintype "passive"))
      (node (ref "C44") (pin "2") (pinfunction "2_2") (pintype "passive"))
      (node (ref "C45") (pin "2") (pinfunction "2_2") (pintype "passive"))
      (node (ref "J1") (pin "1") (pinfunction "VCC_1") (pintype "passive"))
      (node (ref "U17") (pin "5") (pinfunction "VCC_5") (pintype "passive"))
      (node (ref "U18") (pin "1") (pinfunction "IN_1") (pintype "passive"))
      (node (ref "U18") (pin "5") (pinfunction "EN_5") (pintype "passive"))
    )
    (net (code "2") (name "/ADC1") (class "Default")
      (node (ref "C20") (pin "1") (pinfunction "1_1") (pintype "passive"))
      (node (ref "R29") (pin "2") (pinfunction "2_2") (pintype "passive"))
      (node (ref "U3") (pin "10") (pinfunction "PA0/WKUP/ADC123_IN0/T2C1ETR/T5C1/T8ETR_10") (pintype "passive"))
    )
    (net (code "3") (name "/ADC2") (class "Default")
      (node (ref "R29") (pin "5") (pinfunction "5_5") (pintype "passive"))
      (node (ref "R30") (pin "2") (pinfunction "2_2") (pintype "passive"))
      (node (ref "U3") (pin "11") (pinfunction "PA1/ADC123_IN1/T5C2/T2C2_11") (pintype "passive"))
    )
    (net (code "4") (name "/ADC3") (class "Default")
      (node (ref "C21") (pin "2") (pinfunction "2_2") (pintype "passive"))
      (node (ref "R29") (pin "7") (pinfunction "7_7") (pintype "passive"))
      (node (ref "U3") (pin "12") (pinfunction "PA2/ADC123_IN2/USART2_TX/T5C3/T2C3_12") (pintype "passive"))
    )
    (net (code "5") (name "/ADC4") (class "Default")
      (node (ref "C22") (pin "1") (pinfunction "1_1") (pintype "passive"))
      (node (ref "R29") (pin "10") (pinfunction "10_10") (pintype "passive"))
      (node (ref "U3") (pin "13") (pinfunction "PA3/ADC123_IN3/USART2_RX/T5C4/T2C4_13") (pintype "passive"))
    )
    (net (code "6") (name "/ADC5") (class "Default")
      (node (ref "C23") (pin "1") (pinfunction "1_1") (pintype "passive"))
      (node (ref "R31") (pin "2") (pinfunction "2_2") (pintype "passive"))
      (node (ref "U3") (pin "14") (pinfunction "PA4/ADC123_IN4/DAC_OUT1/SPI1_NSS_14") (pintype "passive"))
    )
    (net (code "7") (name "/ADC6") (class "Default")
      (node (ref "R31") (pin "5") (pinfunction "5_5") (pintype "passive"))
      (node (ref "R32") (pin "2") (pinfunction "2_2") (pintype "passive"))
      (node (ref "U3") (pin "15") (pinfunction "PA5/ADC123_IN5/DAC_OUT2/SPI1_SCK_15") (pintype "passive"))
    )
    (net (code "8") (name "/ADC7") (class "Default")
      (node (ref "C24") (pin "2") (pinfunction "2_2") (pintype "passive"))
      (node (ref "R31") (pin "7") (pinfunction "7_7") (pintype "passive"))
      (node (ref "U3") (pin "16") (pinfunction "PA6/ADC123_IN6/SPI1_MISO/T8T1BKIN/T3C1_16") (pintype "passive"))
    )
    (net (code "9") (name "/ADC8") (class "Default")
      (node (ref "C25") (pin "1") (pinfunction "1_1") (pintype "passive"))
      (node (ref "R31") (pin "10") (pinfunction "10_10") (pintype "passive"))
      (node (ref "U3") (pin "17") (pinfunction "PA7/ADC123_IN7/SPI1_MOSI/T8C1N/T3C2/T1C1_17") (pintype "passive"))
    )
    (net (code "10") (name "/ADC9") (class "Default")
      (node (ref "C28") (pin "1") (pinfunction "1_1") (pintype "passive"))
      (node (ref "R33") (pin "2") (pinfunction "2_2") (pintype "passive"))
      (node (ref "U3") (pin "18") (pinfunction "PB0/ADC123_IN8/T3C3/T8C2N/T1C2N_18") (pintype "passive"))
    )
    (net (code "11") (name "/BOOT0") (class "Default")
      (node (ref "R40") (pin "1") (pinfunction "1_1") (pintype "passive"))
      (node (ref "R82") (pin "2") (pinfunction "2_2") (pintype "passive"))
      (node (ref "U3") (pin "44") (pinfunction "BOOT0_44") (pintype "passive"))
    )
    (net (code "12") (name "/BOOT1") (class "Default")
      (node (ref "R81") (pin "1") (pinfunction "1_1") (pintype "passive"))
      (node (ref "R83") (pin "2") (pinfunction "2_2") (pintype "passive"))
      (node (ref "U3") (pin "20") (pinfunction "PB2/BOOT1_20") (pintype "passive"))
    )
    (net (code "13") (name "/CH330_D+") (class "Default")
      (node (ref "J1") (pin "3") (pinfunction "D+_3") (pintype "passive"))
      (node (ref "U17") (pin "1") (pinfunction "UD+_1") (pintype "passive"))
    )
    (net (code "14") (name "/CH330_D-") (class "Default")
      (node (ref "J1") (pin "2") (pinfunction "D-_2") (pintype "passive"))
      (node (ref "U17") (pin "2") (pinfunction "UD-_2") (pintype "passive"))
    )
    (net (code "15") (name "/LED0") (class "Default")
      (node (ref "U14") (pin "2") (pinfunction "2_2") (pintype "passive"))
      (node (ref "U3") (pin "2") (pinfunction "PC13-TAMPER-RTC_2") (pintype "passive"))
    )
    (net (code "16") (name "/LED1") (class "Default")
      (node (ref "U15") (pin "2") (pinfunction "2_2") (pintype "passive"))
      (node (ref "U3") (pin "3") (pinfunction "PC14-OSC32_IN_3") (pintype "passive"))
    )
    (net (code "17") (name "/LED2") (class "Default")
      (node (ref "U16") (pin "2") (pinfunction "2_2") (pintype "passive"))
      (node (ref "U3") (pin "4") (pinfunction "PC15-OSC32_OUT_4") (pintype "passive"))
    )
    (net (code "18") (name "/NRST") (class "Default")
      (node (ref "C108") (pin "1") (pinfunction "1_1") (pintype "passive"))
      (node (ref "U3") (pin "7") (pinfunction "NRST_7") (pintype "passive"))
      (node (ref "Y6") (pin "1") (pinfunction "1_1") (pintype "passive"))
    )
    (net (code "19") (name "/OSCIN") (class "Default")
      (node (ref "C26") (pin "2") (pinfunction "2_2") (pintype "passive"))
      (node (ref "U3") (pin "5") (pinfunction "OSC_IN_5") (pintype "passive"))
      (node (ref "Y1") (pin "2") (pinfunction "2_2") (pintype "passive"))
    )
    (net (code "20") (name "/OSCOUT") (class "Default")
      (node (ref "C27") (pin "2") (pinfunction "2_2") (pintype "passive"))
      (node (ref "U3") (pin "6") (pinfunction "OSC_OUT_6") (pintype "passive"))
      (node (ref "Y1") (pin "1") (pinfunction "1_1") (pintype "passive"))
    )
    (net (code "21") (name "/PA11") (class "Default")
      (node (ref "P1") (pin "4") (pinfunction "4_4") (pintype "passive"))
      (node (ref "U3") (pin "32") (pinfunction "PA11/CAN_RX/T1C4/USBDM_32") (pintype "passive"))
    )
    (net (code "22") (name "/PA12") (class "Default")
      (node (ref "P1") (pin "3") (pinfunction "3_3") (pintype "passive"))
      (node (ref "U3") (pin "33") (pinfunction "PA12/CAN_TX/T1ETR/USBDP_33") (pintype "passive"))
    )
    (net (code "23") (name "/PB3") (class "Default")
      (node (ref "C3") (pin "1") (pinfunction "1_1") (pintype "passive"))
      (node (ref "R1") (pin "2") (pinfunction "2_2") (pintype "passive"))
      (node (ref "R2") (pin "2") (pinfunction "2_2") (pintype "passive"))
      (node (ref "S1") (pin "2") (pinfunction "2_2") (pintype "passive"))
      (node (ref "U3") (pin "39") (pinfunction "PB3/JTDO/SPI3_SCK/I2S3_CK/T2C2/SPI1_SCK_39") (pintype "passive"))
    )
    (net (code "24") (name "/PB4") (class "Default")
      (node (ref "C4") (pin "1") (pinfunction "1_1") (pintype "passive"))
      (node (ref "R3") (pin "2") (pinfunction "2_2") (pintype "passive"))
      (node (ref "R4") (pin "2") (pinfunction "2_2") (pintype "passive"))
      (node (ref "S2") (pin "2") (pinfunction "2_2") (pintype "passive"))
      (node (ref "U3") (pin "40") (pinfunction "PB4/NJTRST/SPI3_MISO/T3C1/SPI1_MISO_40") (pintype "passive"))
    )
    (net (code "25") (name "/PB5") (class "Default")
      (node (ref "C5") (pin "1") (pinfunction "1_1") (pintype "passive"))
      (node (ref "R5") (pin "2") (pinfunction "2_2") (pintype "passive"))
      (node (ref "R6") (pin "2") (pinfunction "2_2") (pintype "passive"))
      (node (ref "S3") (pin "2") (pinfunction "2_2") (pintype "passive"))
      (node (ref "U3") (pin "41") (pinfunction "PB5/I2C1_SMBA/I2S3_SD/SPI3_MOSI/T3C2/SPI_41") (pintype "passive"))
    )
    (net (code "26") (name "/PB6") (class "Default")
      (node (ref "C6") (pin "1") (pinfunction "1_1") (pintype "passive"))
      (node (ref "R7") (pin "2") (pinfunction "2_2") (pintype "passive"))
      (node (ref "R8") (pin "2") (pinfunction "2_2") (pintype "passive"))
      (node (ref "S4") (pin "2") (pinfunction "2_2") (pintype "passive"))
      (node (ref "U3") (pin "42") (pinfunction "PB6/I2C1_SCL/T4C1/USART1_TX_42") (pintype "passive"))
    )
    (net (code "27") (name "/PB7") (class "Default")
      (node (ref "C7") (pin "1") (pinfunction "1_1") (pintype "passive"))
      (node (ref "R10") (pin "2") (pinfunction "2_2") (pintype "passive"))
      (node (ref "R9") (pin "2") (pinfunction "2_2") (pintype "passive"))
      (node (ref "S5") (pin "2") (pinfunction "2_2") (pintype "passive"))
      (node (ref "U3") (pin "43") (pinfunction "PB7/I2C1_SDA/FSMC_NADV/USART1_RX_43") (pintype "passive"))
    )
    (net (code "28") (name "/PB8") (class "Default")
      (node (ref "C8") (pin "1") (pinfunction "1_1") (pintype "passive"))
      (node (ref "R11") (pin "2") (pinfunction "2_2") (pintype "passive"))
      (node (ref "R12") (pin "2") (pinfunction "2_2") (pintype "passive"))
      (node (ref "S6") (pin "2") (pinfunction "2_2") (pintype "passive"))
      (node (ref "U3") (pin "45") (pinfunction "PB8/SDIO_D4/I2C1_SCL/T4C3(7)/CAN_RX_45") (pintype "passive"))
    )
    (net (code "29") (name "/PB9") (class "Default")
      (node (ref "C9") (pin "1") (pinfunction "1_1") (pintype "passive"))
      (node (ref "R13") (pin "2") (pinfunction "2_2") (pintype "passive"))
      (node (ref "R14") (pin "2") (pinfunction "2_2") (pintype "passive"))
      (node (ref "S7") (pin "2") (pinfunction "2_2") (pintype "passive"))
      (node (ref "U3") (pin "46") (pinfunction "PB9/SDIO_D5/I2C1_SDA/T4C4/CAN_TX_46") (pintype "passive"))
    )
    (net (code "30") (name "/PB10") (class "Default")
      (node (ref "C10") (pin "1") (pinfunction "1_1") (pintype "passive"))
      (node (ref "R15") (pin "2") (pinfunction "2_2") (pintype "passive"))
      (node (ref "R16") (pin "2") (pinfunction "2_2") (pintype "passive"))
      (node (ref "S8") (pin "2") (pinfunction "2_2") (pintype "passive"))
      (node (ref "U3") (pin "21") (pinfunction "PB10/USART3_TX/I2C2_SCL/T2C3_21") (pintype "passive"))
    )
    (net (code "31") (name "/PB11") (class "Default")
      (node (ref "C11") (pin "1") (pinfunction "1_1") (pintype "passive"))
      (node (ref "R17") (pin "2") (pinfunction "2_2") (pintype "passive"))
      (node (ref "R18") (pin "2") (pinfunction "2_2") (pintype "passive"))
      (node (ref "S9") (pin "2") (pinfunction "2_2") (pintype "passive"))
      (node (ref "U3") (pin "22") (pinfunction "PB11/USART3_RX/I2C2_SDA/T2C4_22") (pintype "passive"))
    )
    (net (code "32") (name "/PB12") (class "Default")
      (node (ref "C12") (pin "1") (pinfunction "1_1") (pintype "passive"))
      (node (ref "R19") (pin "2") (pinfunction "2_2") (pintype "passive"))
      (node (ref "R20") (pin "2") (pinfunction "2_2") (pintype "passive"))
      (node (ref "S10") (pin "2") (pinfunction "2_2") (pintype "passive"))
      (node (ref "U3") (pin "25") (pinfunction "PB12/I2S2_WS/T1BKIN/SPI2_NSS/I2C2_SMBA_25") (pintype "passive"))
    )
    (net (code "33") (name "/PB13") (class "Default")
      (node (ref "C13") (pin "1") (pinfunction "1_1") (pintype "passive"))
      (node (ref "R21") (pin "2") (pinfunction "2_2") (pintype "passive"))
      (node (ref "R22") (pin "2") (pinfunction "2_2") (pintype "passive"))
      (node (ref "S11") (pin "2") (pinfunction "2_2") (pintype "passive"))
      (node (ref "U3") (pin "26") (pinfunction "PB13/I2S2_CK/T1CH1N/SPI2_SCK_26") (pintype "passive"))
    )
    (net (code "34") (name "/PB14") (class "Default")
      (node (ref "C14") (pin "1") (pinfunction "1_1") (pintype "passive"))
      (node (ref "R23") (pin "2") (pinfunction "2_2") (pintype "passive"))
      (node (ref "R24") (pin "2") (pinfunction "2_2") (pintype "passive"))
      (node (ref "S12") (pin "2") (pinfunction "2_2") (pintype "passive"))
      (node (ref "U3") (pin "27") (pinfunction "PB14/T1CH2N/SPI2_MISO_27") (pintype "passive"))
    )
    (net (code "35") (name "/SWCLK") (class "Default")
      (node (ref "P4") (pin "2") (pinfunction "2_2") (pintype "passive"))
      (node (ref "U3") (pin "37") (pinfunction "PA14/JTCK/SWCLK_37") (pintype "passive"))
    )
    (net (code "36") (name "/SWIO") (class "Default")
      (node (ref "P4") (pin "3") (pinfunction "3_3") (pintype "passive"))
      (node (ref "U3") (pin "34") (pinfunction "PA13/JTMS/SWDIO_34") (pintype "passive"))
    )
    (net (code "37") (name "/U1_RX") (class "Default")
      (node (ref "P2") (pin "2") (pinfunction "2_2") (pintype "passive"))
      (node (ref "U17") (pin "6") (pinfunction "TXD_6") (pintype "passive"))
      (node (ref "U3") (pin "31") (pinfunction "PA10/T1C3/USART1_RX_31") (pintype "passive"))
    )
    (net (code "38") (name "/U1_TX") (class "Default")
      (node (ref "P2") (pin "3") (pinfunction "3_3") (pintype "passive"))
      (node (ref "U17") (pin "7") (pinfunction "RXD_7") (pintype "passive"))
      (node (ref "U3") (pin "30") (pinfunction "PA9/T1C2/USART1_TX_30") (pintype "passive"))
    )
    (net (code "39") (name "AGND") (class "Default")
      (node (ref "C1") (pin "1") (pinfunction "1_1") (pintype "passive"))
      (node (ref "C10") (pin "2") (pinfunction "2_2") (pintype "passive"))
      (node (ref "C102") (pin "2") (pinfunction "2_2") (pintype "passive"))
      (node (ref "C103") (pin "2") (pinfunction "2_2") (pintype "passive"))
      (node (ref "C104") (pin "2") (pinfunction "2_2") (pintype "passive"))
      (node (ref "C108") (pin "2") (pinfunction "2_2") (pintype "passive"))
      (node (ref "C11") (pin "2") (pinfunction "2_2") (pintype "passive"))
      (node (ref "C12") (pin "2") (pinfunction "2_2") (pintype "passive"))
      (node (ref "C13") (pin "2") (pinfunction "2_2") (pintype "passive"))
      (node (ref "C14") (pin "2") (pinfunction "2_2") (pintype "passive"))
      (node (ref "C15") (pin "1") (pinfunction "1_1") (pintype "passive"))
      (node (ref "C16") (pin "1") (pinfunction "1_1") (pintype "passive"))
      (node (ref "C17") (pin "2") (pinfunction "2_2") (pintype "passive"))
      (node (ref "C18") (pin "1") (pinfunction "1_1") (pintype "passive"))
      (node (ref "C19") (pin "1") (pinfunction "1_1") (pintype "passive"))
      (node (ref "C2") (pin "1") (pinfunction "1_1") (pintype "passive"))
      (node (ref "C20") (pin "2") (pinfunction "2_2") (pintype "passive"))
      (node (ref "C22") (pin "2") (pinfunction "2_2") (pintype "passive"))
      (node (ref "C23") (pin "2") (pinfunction "2_2") (pintype "passive"))
      (node (ref "C25") (pin "2") (pinfunction "2_2") (pintype "passive"))
      (node (ref "C26") (pin "1") (pinfunction "1_1") (pintype "passive"))
      (node (ref "C27") (pin "1") (pinfunction "1_1") (pintype "passive"))
      (node (ref "C28") (pin "2") (pinfunction "2_2") (pintype "passive"))
      (node (ref "C3") (pin "2") (pinfunction "2_2") (pintype "passive"))
      (node (ref "C30") (pin "1") (pinfunction "1_1") (pintype "passive"))
      (node (ref "C4") (pin "2") (pinfunction "2_2") (pintype "passive"))
      (node (ref "C43") (pin "1") (pinfunction "1_1") (pintype "passive"))
      (node (ref "C44") (pin "1") (pinfunction "1_1") (pintype "passive"))
      (node (ref "C45") (pin "1") (pinfunction "1_1") (pintype "passive"))
      (node (ref "C46") (pin "1") (pinfunction "1_1") (pintype "passive"))
      (node (ref "C47") (pin "1") (pinfunction "1_1") (pintype "passive"))
      (node (ref "C48") (pin "1") (pinfunction "1_1") (pintype "passive"))
      (node (ref "C49") (pin "1") (pinfunction "1_1") (pintype "passive"))
      (node (ref "C5") (pin "2") (pinfunction "2_2") (pintype "passive"))
      (node (ref "C6") (pin "2") (pinfunction "2_2") (pintype "passive"))
      (node (ref "C66") (pin "2") (pinfunction "2_2") (pintype "passive"))
      (node (ref "C67") (pin "2") (pinfunction "2_2") (pintype "passive"))
      (node (ref "C68") (pin "2") (pinfunction "2_2") (pintype "passive"))
      (node (ref "C69") (pin "2") (pinfunction "2_2") (pintype "passive"))
      (node (ref "C7") (pin "2") (pinfunction "2_2") (pintype "passive"))
      (node (ref "C70") (pin "2") (pinfunction "2_2") (pintype "passive"))
      (node (ref "C71") (pin "2") (pinfunction "2_2") (pintype "passive"))
      (node (ref "C72") (pin "2") (pinfunction "2_2") (pintype "passive"))
      (node (ref "C73") (pin "2") (pinfunction "2_2") (pintype "passive"))
      (node (ref "C8") (pin "2") (pinfunction "2_2") (pintype "passive"))
      (node (ref "C9") (pin "2") (pinfunction "2_2") (pintype "passive"))
      (node (ref "J1") (pin "5") (pinfunction "GND_5") (pintype "passive"))
      (node (ref "P1") (pin "1") (pinfunction "1_1") (pintype "passive"))
      (node (ref "P2") (pin "1") (pinfunction "1_1") (pintype "passive"))
      (node (ref "P4") (pin "1") (pinfunction "1_1") (pintype "passive"))
      (node (ref "R10") (pin "1") (pinfunction "1_1") (pintype "passive"))
      (node (ref "R12") (pin "1") (pinfunction "1_1") (pintype "passive"))
      (node (ref "R14") (pin "1") (pinfunction "1_1") (pintype "passive"))
      (node (ref "R16") (pin "1") (pinfunction "1_1") (pintype "passive"))
      (node (ref "R18") (pin "1") (pinfunction "1_1") (pintype "passive"))
      (node (ref "R2") (pin "1") (pinfunction "1_1") (pintype "passive"))
      (node (ref "R20") (pin "1") (pinfunction "1_1") (pintype "passive"))
      (node (ref "R22") (pin "1") (pinfunction "1_1") (pintype "passive"))
      (node (ref "R24") (pin "1") (pinfunction "1_1") (pintype "passive"))
      (node (ref "R29") (pin "11") (pinfunction "11_11") (pintype "passive"))
      (node (ref "R29") (pin "3") (pinfunction "3_3") (pintype "passive"))
      (node (ref "R29") (pin "6") (pinfunction "6_6") (pintype "passive"))
      (node (ref "R30") (pin "1") (pinfunction "1_1") (pintype "passive"))
      (node (ref "R31") (pin "11") (pinfunction "11_11") (pintype "passive"))
      (node (ref "R31") (pin "3") (pinfunction "3_3") (pintype "passive"))
      (node (ref "R31") (pin "6") (pinfunction "6_6") (pintype "passive"))
      (node (ref "R32") (pin "1") (pinfunction "1_1") (pintype "passive"))
      (node (ref "R33") (pin "3") (pinfunction "3_3") (pintype "passive"))
      (node (ref "R4") (pin "1") (pinfunction "1_1") (pintype "passive"))
      (node (ref "R6") (pin "1") (pinfunction "1_1") (pintype "passive"))
      (node (ref "R8") (pin "1") (pinfunction "1_1") (pintype "passive"))
      (node (ref "R82") (pin "1") (pinfunction "1_1") (pintype "passive"))
      (node (ref "R83") (pin "1") (pinfunction "1_1") (pintype "passive"))
      (node (ref "R88") (pin "2") (pinfunction "2_2") (pintype "passive"))
      (node (ref "U1") (pin "2") (pinfunction "2_2") (pintype "passive"))
      (node (ref "U10") (pin "2") (pinfunction "2_2") (pintype "passive"))
      (node (ref "U11") (pin "2") (pinfunction "2_2") (pintype "passive"))
      (node (ref "U12") (pin "2") (pinfunction "2_2") (pintype "passive"))
      (node (ref "U13") (pin "2") (pinfunction "2_2") (pintype "passive"))
      (node (ref "U17") (pin "3") (pinfunction "GND_3") (pintype "passive"))
      (node (ref "U18") (pin "3") (pinfunction "GND_3") (pintype "passive"))
      (node (ref "U18") (pin "6") (pinfunction "GND_6") (pintype "passive"))
      (node (ref "U2") (pin "2") (pinfunction "2_2") (pintype "passive"))
      (node (ref "U21") (pin "2") (pinfunction "2_2") (pintype "passive"))
      (node (ref "U3") (pin "23") (pinfunction "VSS_1_23") (pintype "passive"))
      (node (ref "U3") (pin "35") (pinfunction "VSS_2_35") (pintype "passive"))
      (node (ref "U3") (pin "47") (pinfunction "VSS_3_47") (pintype "passive"))
      (node (ref "U3") (pin "8") (pinfunction "VSSA_8") (pintype "passive"))
      (node (ref "U4") (pin "2") (pinfunction "2_2") (pintype "passive"))
      (node (ref "U5") (pin "2") (pinfunction "2_2") (pintype "passive"))
      (node (ref "U6") (pin "2") (pinfunction "2_2") (pintype "passive"))
      (node (ref "U7") (pin "2") (pinfunction "2_2") (pintype "passive"))
      (node (ref "U8") (pin "2") (pinfunction "2_2") (pintype "passive"))
      (node (ref "U9") (pin "2") (pinfunction "2_2") (pintype "passive"))
      (node (ref "Y1") (pin "3") (pinfunction "3_3") (pintype "passive"))
      (node (ref "Y1") (pin "4") (pinfunction "4_4") (pintype "passive"))
      (node (ref "Y6") (pin "2") (pinfunction "2_2") (pintype "passive"))
    )
    (net (code "40") (name "Net-(R1-Pad1)") (class "Default")
      (node (ref "R1") (pin "1") (pinfunction "1_1") (pintype "passive"))
      (node (ref "U21") (pin "1") (pinfunction "1_1") (pintype "passive"))
    )
    (net (code "41") (name "Net-(R3-Pad1)") (class "Default")
      (node (ref "R3") (pin "1") (pinfunction "1_1") (pintype "passive"))
      (node (ref "U1") (pin "1") (pinfunction "1_1") (pintype "passive"))
    )
    (net (code "42") (name "Net-(R5-Pad1)") (class "Default")
      (node (ref "R5") (pin "1") (pinfunction "1_1") (pintype "passive"))
      (node (ref "U2") (pin "1") (pinfunction "1_1") (pintype "passive"))
    )
    (net (code "43") (name "Net-(R7-Pad1)") (class "Default")
      (node (ref "R7") (pin "1") (pinfunction "1_1") (pintype "passive"))
      (node (ref "U4") (pin "1") (pinfunction "1_1") (pintype "passive"))
    )
    (net (code "44") (name "Net-(R9-Pad1)") (class "Default")
      (node (ref "R9") (pin "1") (pinfunction "1_1") (pintype "passive"))
      (node (ref "U5") (pin "1") (pinfunction "1_1") (pintype "passive"))
    )
    (net (code "45") (name "Net-(R11-Pad1)") (class "Default")
      (node (ref "R11") (pin "1") (pinfunction "1_1") (pintype "passive"))
      (node (ref "U6") (pin "1") (pinfunction "1_1") (pintype "passive"))
    )
    (net (code "46") (name "Net-(R13-Pad1)") (class "Default")
      (node (ref "R13") (pin "1") (pinfunction "1_1") (pintype "passive"))
      (node (ref "U7") (pin "1") (pinfunction "1_1") (pintype "passive"))
    )
    (net (code "47") (name "Net-(R15-Pad1)") (class "Default")
      (node (ref "R15") (pin "1") (pinfunction "1_1") (pintype "passive"))
      (node (ref "U8") (pin "1") (pinfunction "1_1") (pintype "passive"))
    )
    (net (code "48") (name "Net-(R17-Pad1)") (class "Default")
      (node (ref "R17") (pin "1") (pinfunction "1_1") (pintype "passive"))
      (node (ref "U9") (pin "1") (pinfunction "1_1") (pintype "passive"))
    )
    (net (code "49") (name "Net-(R19-Pad1)") (class "Default")
      (node (ref "R19") (pin "1") (pinfunction "1_1") (pintype "passive"))
      (node (ref "U10") (pin "1") (pinfunction "1_1") (pintype "passive"))
    )
    (net (code "50") (name "Net-(R21-Pad1)") (class "Default")
      (node (ref "R21") (pin "1") (pinfunction "1_1") (pintype "passive"))
      (node (ref "U11") (pin "1") (pinfunction "1_1") (pintype "passive"))
    )
    (net (code "51") (name "Net-(R23-Pad1)") (class "Default")
      (node (ref "R23") (pin "1") (pinfunction "1_1") (pintype "passive"))
      (node (ref "U12") (pin "1") (pinfunction "1_1") (pintype "passive"))
    )
    (net (code "52") (name "Net-(R25-Pad2)") (class "Default")
      (node (ref "R25") (pin "2") (pinfunction "2_2") (pintype "passive"))
      (node (ref "U13") (pin "1") (pinfunction "1_1") (pintype "passive"))
    )
    (net (code "53") (name "Net-(R26-Pad2)") (class "Default")
      (node (ref "R26") (pin "2") (pinfunction "2_2") (pintype "passive"))
      (node (ref "U14") (pin "1") (pinfunction "1_1") (pintype "passive"))
    )
    (net (code "54") (name "Net-(R27-Pad2)") (class "Default")
      (node (ref "R27") (pin "2") (pinfunction "2_2") (pintype "passive"))
      (node (ref "U15") (pin "1") (pinfunction "1_1") (pintype "passive"))
    )
    (net (code "55") (name "Net-(R28-Pad2)") (class "Default")
      (node (ref "R28") (pin "2") (pinfunction "2_2") (pintype "passive"))
      (node (ref "U16") (pin "1") (pinfunction "1_1") (pintype "passive"))
    )
    (net (code "56") (name "Net-(U17-V3)") (class "Default")
      (node (ref "C17") (pin "1") (pinfunction "1_1") (pintype "passive"))
      (node (ref "U17") (pin "8") (pinfunction "V3_8") (pintype "passive"))
    )
    (net (code "57") (name "Net-(U18-FB)") (class "Default")
      (node (ref "R51") (pin "2") (pinfunction "2_2") (pintype "passive"))
      (node (ref "R88") (pin "1") (pinfunction "1_1") (pintype "passive"))
      (node (ref "U18") (pin "4") (pinfunction "FB_4") (pintype "passive"))
    )
    (net (code "58") (name "VCC_3.3V") (class "Default")
      (node (ref "C102") (pin "1") (pinfunction "1_1") (pintype "passive"))
      (node (ref "C103") (pin "1") (pinfunction "1_1") (pintype "passive"))
      (node (ref "C104") (pin "1") (pinfunction "1_1") (pintype "passive"))
      (node (ref "C18") (pin "2") (pinfunction "2_2") (pintype "passive"))
      (node (ref "C19") (pin "2") (pinfunction "2_2") (pintype "passive"))
      (node (ref "C2") (pin "2") (pinfunction "2_2") (pintype "passive"))
      (node (ref "C21") (pin "1") (pinfunction "1_1") (pintype "passive"))
      (node (ref "C24") (pin "1") (pinfunction "1_1") (pintype "passive"))
      (node (ref "C30") (pin "2") (pinfunction "2_2") (pintype "passive"))
      (node (ref "C46") (pin "2") (pinfunction "2_2") (pintype "passive"))
      (node (ref "C47") (pin "2") (pinfunction "2_2") (pintype "passive"))
      (node (ref "C48") (pin "2") (pinfunction "2_2") (pintype "passive"))
      (node (ref "C49") (pin "2") (pinfunction "2_2") (pintype "passive"))
      (node (ref "C66") (pin "1") (pinfunction "1_1") (pintype "passive"))
      (node (ref "C67") (pin "1") (pinfunction "1_1") (pintype "passive"))
      (node (ref "C68") (pin "1") (pinfunction "1_1") (pintype "passive"))
      (node (ref "C69") (pin "1") (pinfunction "1_1") (pintype "passive"))
      (node (ref "C70") (pin "1") (pinfunction "1_1") (pintype "passive"))
      (node (ref "C71") (pin "1") (pinfunction "1_1") (pintype "passive"))
      (node (ref "C72") (pin "1") (pinfunction "1_1") (pintype "passive"))
      (node (ref "C73") (pin "1") (pinfunction "1_1") (pintype "passive"))
      (node (ref "P1") (pin "2") (pinfunction "2_2") (pintype "passive"))
      (node (ref "P2") (pin "4") (pinfunction "4_4") (pintype "passive"))
      (node (ref "P4") (pin "4") (pinfunction "4_4") (pintype "passive"))
      (node (ref "R25") (pin "1") (pinfunction "1_1") (pintype "passive"))
      (node (ref "R26") (pin "1") (pinfunction "1_1") (pintype "passive"))
      (node (ref "R27") (pin "1") (pinfunction "1_1") (pintype "passive"))
      (node (ref "R28") (pin "1") (pinfunction "1_1") (pintype "passive"))
      (node (ref "R29") (pin "1") (pinfunction "1_1") (pintype "passive"))
      (node (ref "R29") (pin "4") (pinfunction "4_4") (pintype "passive"))
      (node (ref "R29") (pin "8") (pinfunction "8_8") (pintype "passive"))
      (node (ref "R29") (pin "9") (pinfunction "9_9") (pintype "passive"))
      (node (ref "R31") (pin "1") (pinfunction "1_1") (pintype "passive"))
      (node (ref "R31") (pin "4") (pinfunction "4_4") (pintype "passive"))
      (node (ref "R31") (pin "8") (pinfunction "8_8") (pintype "passive"))
      (node (ref "R31") (pin "9") (pinfunction "9_9") (pintype "passive"))
      (node (ref "R33") (pin "1") (pinfunction "1_1") (pintype "passive"))
      (node (ref "R40") (pin "2") (pinfunction "2_2") (pintype "passive"))
      (node (ref "R51") (pin "1") (pinfunction "1_1") (pintype "passive"))
      (node (ref "R81") (pin "2") (pinfunction "2_2") (pintype "passive"))
      (node (ref "S1") (pin "3") (pinfunction "3_3") (pintype "passive"))
      (node (ref "S10") (pin "3") (pinfunction "3_3") (pintype "passive"))
      (node (ref "S11") (pin "3") (pinfunction "3_3") (pintype "passive"))
      (node (ref "S12") (pin "3") (pinfunction "3_3") (pintype "passive"))
      (node (ref "S2") (pin "3") (pinfunction "3_3") (pintype "passive"))
      (node (ref "S3") (pin "3") (pinfunction "3_3") (pintype "passive"))
      (node (ref "S4") (pin "3") (pinfunction "3_3") (pintype "passive"))
      (node (ref "S5") (pin "3") (pinfunction "3_3") (pintype "passive"))
      (node (ref "S6") (pin "3") (pinfunction "3_3") (pintype "passive"))
      (node (ref "S7") (pin "3") (pinfunction "3_3") (pintype "passive"))
      (node (ref "S8") (pin "3") (pinfunction "3_3") (pintype "passive"))
      (node (ref "S9") (pin "3") (pinfunction "3_3") (pintype "passive"))
      (node (ref "U18") (pin "2") (pinfunction "OUT_2") (pintype "passive"))
      (node (ref "U3") (pin "24") (pinfunction "VDD_1_24") (pintype "passive"))
      (node (ref "U3") (pin "36") (pinfunction "VDD_2_36") (pintype "passive"))
      (node (ref "U3") (pin "48") (pinfunction "VDD_3_48") (pintype "passive"))
      (node (ref "U3") (pin "9") (pinfunction "VDDA_9") (pintype "passive"))
    )
    (net (code "59") (name "unconnected-(J1-EP-Pad6)") (class "Default")
      (node (ref "J1") (pin "6") (pinfunction "EP_6") (pintype "passive"))
    )
    (net (code "60") (name "unconnected-(J1-EP-Pad7)") (class "Default")
      (node (ref "J1") (pin "7") (pinfunction "EP_7") (pintype "passive"))
    )
    (net (code "61") (name "unconnected-(J1-ID-Pad4)") (class "Default")
      (node (ref "J1") (pin "4") (pinfunction "ID_4") (pintype "passive+no_connect"))
    )
    (net (code "62") (name "unconnected-(R33-Pad4)") (class "Default")
      (node (ref "R33") (pin "4") (pinfunction "4_4") (pintype "passive+no_connect"))
    )
    (net (code "63") (name "unconnected-(R33-Pad5)") (class "Default")
      (node (ref "R33") (pin "5") (pinfunction "5_5") (pintype "passive+no_connect"))
    )
    (net (code "64") (name "unconnected-(S1-Pad1)") (class "Default")
      (node (ref "S1") (pin "1") (pinfunction "1_1") (pintype "passive+no_connect"))
    )
    (net (code "65") (name "unconnected-(S2-Pad1)") (class "Default")
      (node (ref "S2") (pin "1") (pinfunction "1_1") (pintype "passive+no_connect"))
    )
    (net (code "66") (name "unconnected-(S3-Pad1)") (class "Default")
      (node (ref "S3") (pin "1") (pinfunction "1_1") (pintype "passive+no_connect"))
    )
    (net (code "67") (name "unconnected-(S4-Pad1)") (class "Default")
      (node (ref "S4") (pin "1") (pinfunction "1_1") (pintype "passive+no_connect"))
    )
    (net (code "68") (name "unconnected-(S5-Pad1)") (class "Default")
      (node (ref "S5") (pin "1") (pinfunction "1_1") (pintype "passive+no_connect"))
    )
    (net (code "69") (name "unconnected-(S6-Pad1)") (class "Default")
      (node (ref "S6") (pin "1") (pinfunction "1_1") (pintype "passive+no_connect"))
    )
    (net (code "70") (name "unconnected-(S7-Pad1)") (class "Default")
      (node (ref "S7") (pin "1") (pinfunction "1_1") (pintype "passive+no_connect"))
    )
    (net (code "71") (name "unconnected-(S8-Pad1)") (class "Default")
      (node (ref "S8") (pin "1") (pinfunction "1_1") (pintype "passive+no_connect"))
    )
    (net (code "72") (name "unconnected-(S9-Pad1)") (class "Default")
      (node (ref "S9") (pin "1") (pinfunction "1_1") (pintype "passive+no_connect"))
    )
    (net (code "73") (name "unconnected-(S10-Pad1)") (class "Default")
      (node (ref "S10") (pin "1") (pinfunction "1_1") (pintype "passive+no_connect"))
    )
    (net (code "74") (name "unconnected-(S11-Pad1)") (class "Default")
      (node (ref "S11") (pin "1") (pinfunction "1_1") (pintype "passive+no_connect"))
    )
    (net (code "75") (name "unconnected-(S12-Pad1)") (class "Default")
      (node (ref "S12") (pin "1") (pinfunction "1_1") (pintype "passive+no_connect"))
    )
    (net (code "76") (name "unconnected-(U3-PA8{slash}T1C1{slash}MCO-Pad29)") (class "Default")
      (node (ref "U3") (pin "29") (pinfunction "PA8/T1C1/MCO_29") (pintype "passive"))
    )
    (net (code "77") (name "unconnected-(U3-PA15{slash}JTDI{slash}I2S3_WS{slash}JTDI{slash}T2C1ETR{slash}SPI3_NSS-Pad38)") (class "Default")
      (node (ref "U3") (pin "38") (pinfunction "PA15/JTDI/I2S3_WS/JTDI/T2C1ETR/SPI3_NSS_38") (pintype "passive"))
    )
    (net (code "78") (name "unconnected-(U3-PB1{slash}ADC123_IN9{slash}T3C4{slash}T8C3N{slash}T1C3N-Pad19)") (class "Default")
      (node (ref "U3") (pin "19") (pinfunction "PB1/ADC123_IN9/T3C4/T8C3N/T1C3N_19") (pintype "passive+no_connect"))
    )
    (net (code "79") (name "unconnected-(U3-PB15{slash}I2S2_SD{slash}T1CH3N{slash}SPI2_MOSI-Pad28)") (class "Default")
      (node (ref "U3") (pin "28") (pinfunction "PB15/I2S2_SD/T1CH3N/SPI2_MOSI_28") (pintype "passive"))
    )
    (net (code "80") (name "unconnected-(U3-VBAT-Pad1)") (class "Default")
      (node (ref "U3") (pin "1") (pinfunction "VBAT_1") (pintype "passive"))
    )
    (net (code "81") (name "unconnected-(U17-RTS-Pad4)") (class "Default")
      (node (ref "U17") (pin "4") (pinfunction "RTS_4") (pintype "passive"))
    )
  )
)
